# schematic.net
KiCad netlist of a schematic drawn in Altium Designer
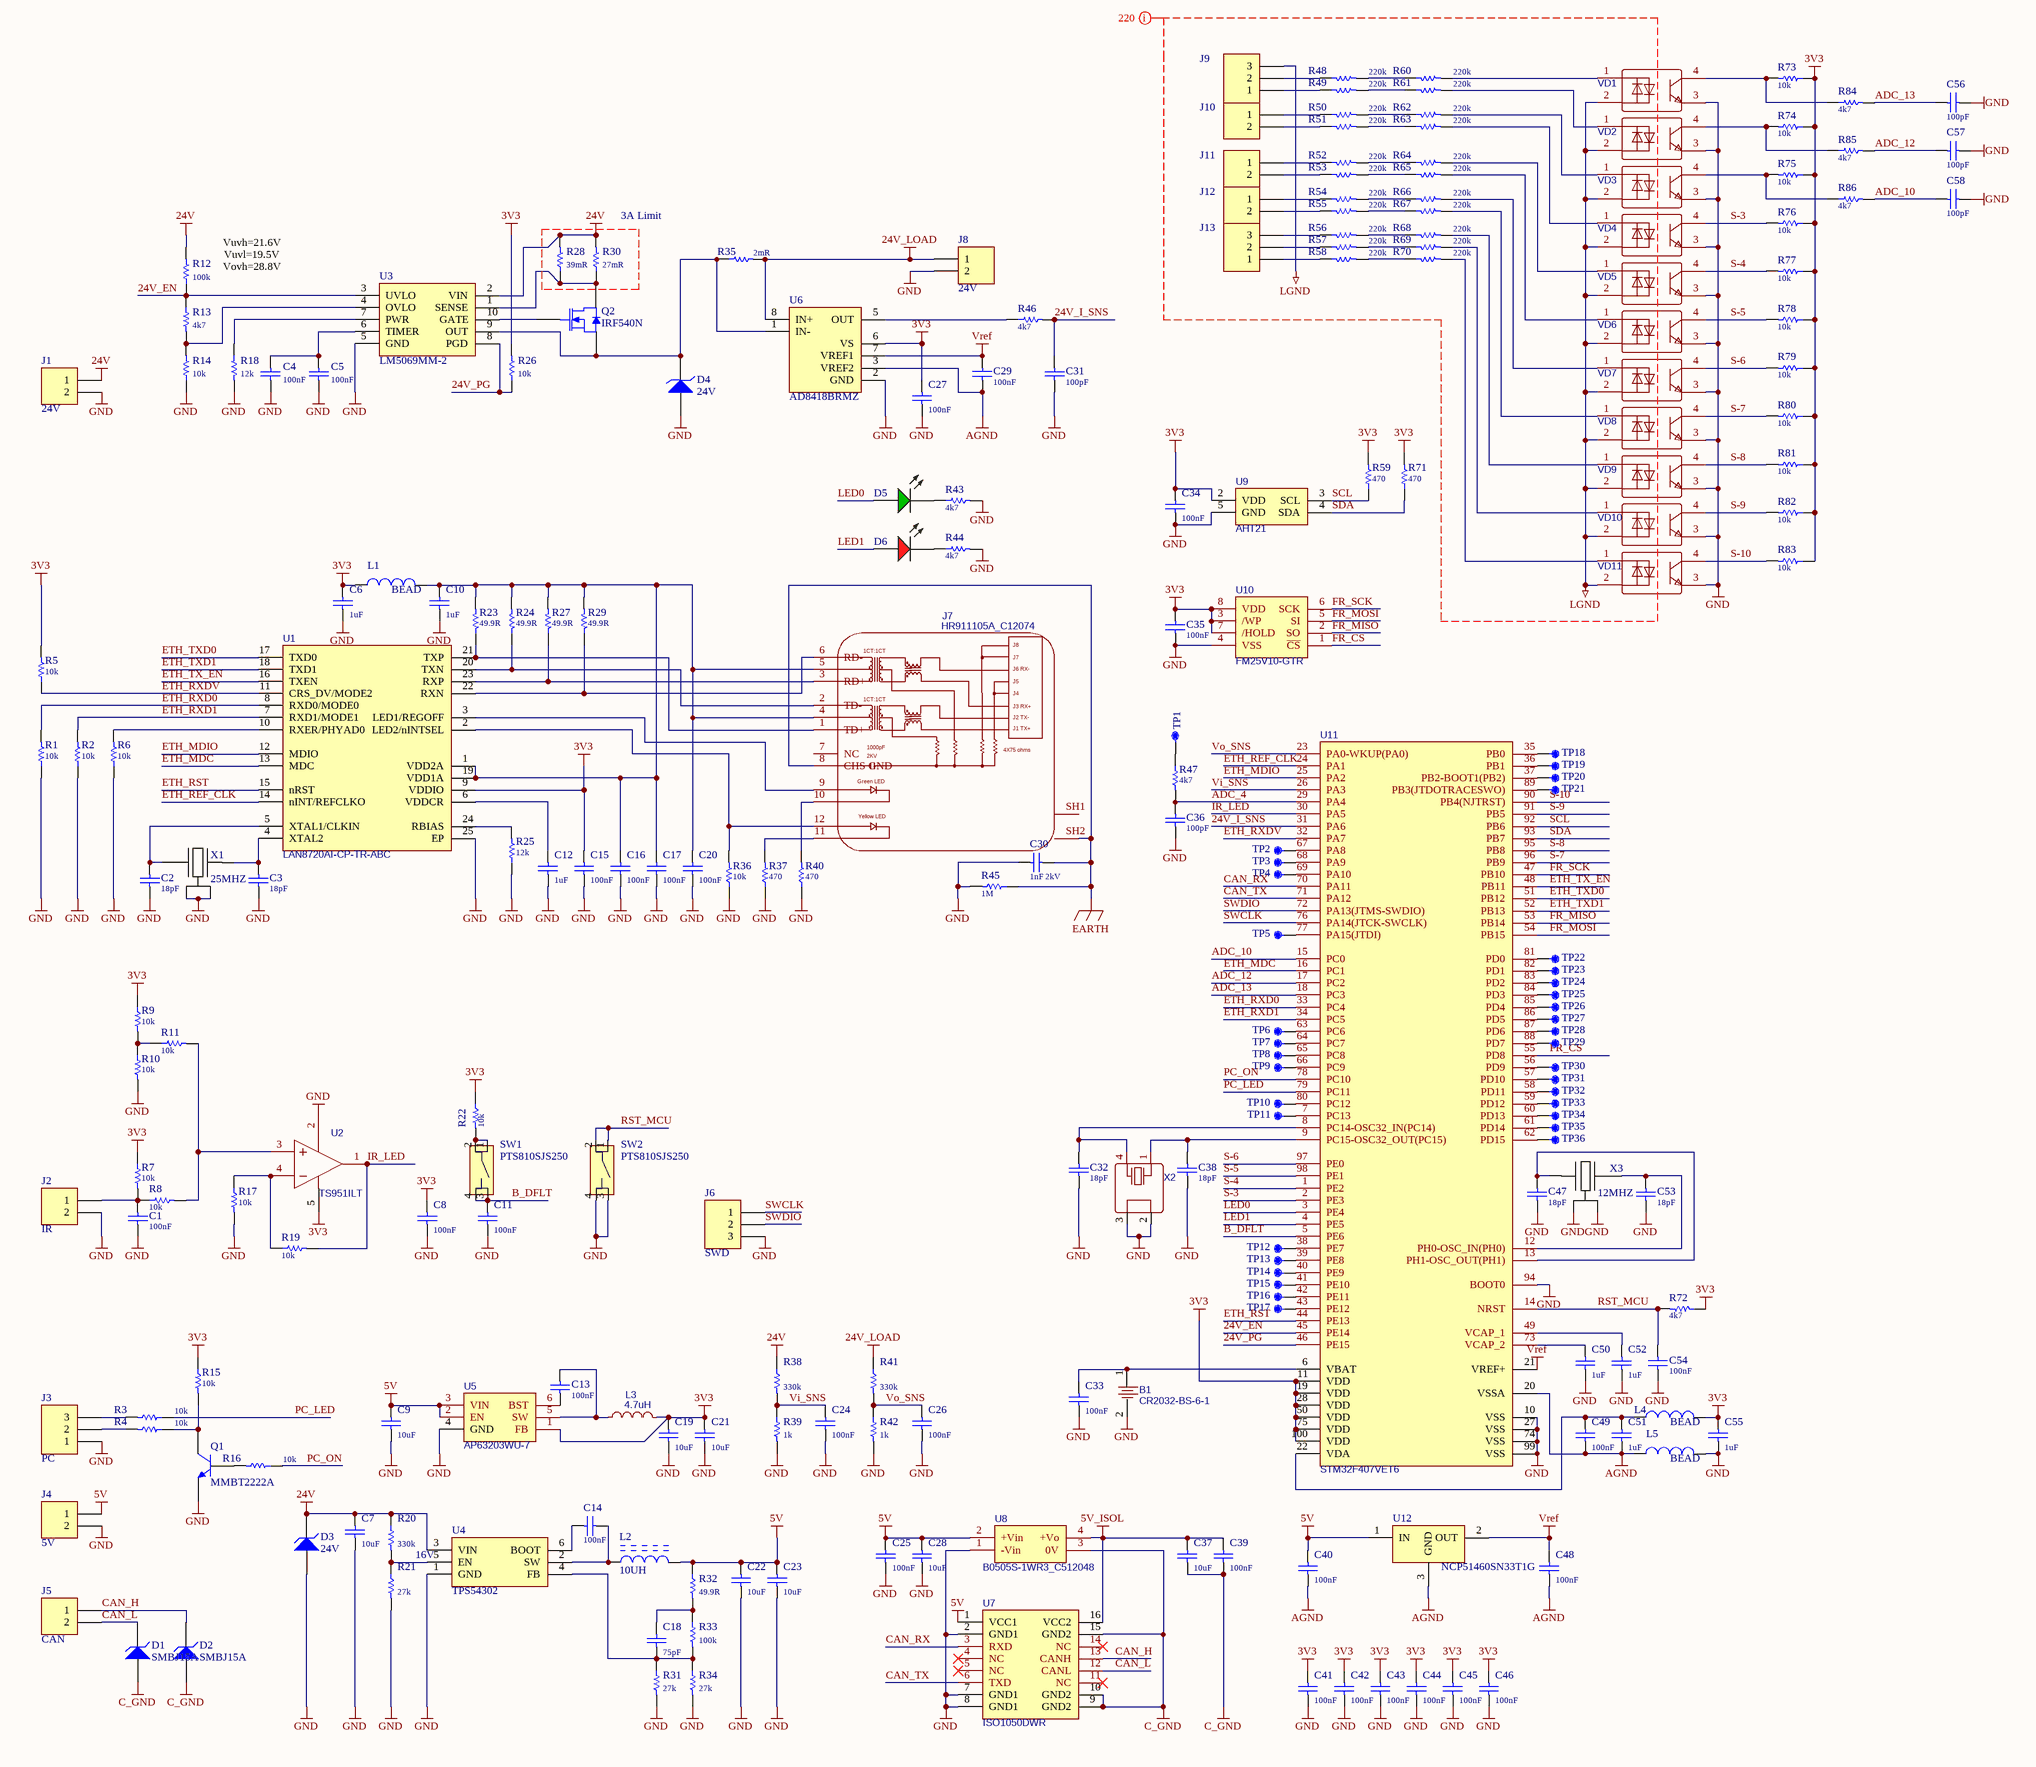
[diagram p0: schematic.SchDoc]

(export (version "E")
  (design (tool "Eeschema 10.0.6"))
  (components
    (comp (ref "B1")
      (value "CR2032-BS-6-1")
      (footprint "BAT-TH_CR2032-BS-6-1")
      (libsource (lib "altium-import") (part "root_3_CR2032-BS-6-1_"))
    )
    (comp (ref "C1")
      (value "100nF")
      (footprint "C0603")
      (description "100nF 0603")
      (libsource (lib "Miscellaneous Devices") (part "CAP"))
    )
    (comp (ref "C2")
      (value "18pF")
      (footprint "C0402")
      (description "10pF 0402")
      (libsource (lib "Miscellaneous Devices") (part "CAP"))
    )
    (comp (ref "C3")
      (value "18pF")
      (footprint "C0402")
      (description "10pF 0402")
      (libsource (lib "Miscellaneous Devices") (part "CAP"))
    )
    (comp (ref "C4")
      (value "100nF")
      (footprint "C0402")
      (description "100nF 0402")
      (libsource (lib "Miscellaneous Devices") (part "CAP"))
    )
    (comp (ref "C5")
      (value "100nF")
      (footprint "C0402")
      (description "100nF 0402")
      (libsource (lib "Miscellaneous Devices") (part "CAP"))
    )
    (comp (ref "C6")
      (value "1uF")
      (footprint "C0603")
      (description "1uF 0603")
      (libsource (lib "Miscellaneous Devices") (part "CAP"))
    )
    (comp (ref "C7")
      (value "10uF")
      (footprint "C1206")
      (description "10uF 1206")
      (libsource (lib "Miscellaneous Devices") (part "CAP"))
    )
    (comp (ref "C8")
      (value "100nF")
      (footprint "C0402")
      (description "100nF 0402")
      (libsource (lib "Miscellaneous Devices") (part "CAP"))
    )
    (comp (ref "C9")
      (value "10uF")
      (footprint "C1206")
      (description "10uF 1206")
      (libsource (lib "Miscellaneous Devices") (part "CAP"))
    )
    (comp (ref "C10")
      (value "1uF")
      (footprint "C0603")
      (description "1uF 0603")
      (libsource (lib "Miscellaneous Devices") (part "CAP"))
    )
    (comp (ref "C11")
      (value "100nF")
      (footprint "C0402")
      (description "100nF 0402")
      (libsource (lib "Miscellaneous Devices") (part "CAP"))
    )
    (comp (ref "C12")
      (value "1uF")
      (footprint "C0603")
      (description "1uF 0603")
      (libsource (lib "Miscellaneous Devices") (part "CAP"))
    )
    (comp (ref "C13")
      (value "100nF")
      (footprint "C0402")
      (description "100nF 0402")
      (libsource (lib "Miscellaneous Devices") (part "CAP"))
    )
    (comp (ref "C14")
      (value "100nF")
      (footprint "C0603")
      (description "100nF 0603")
      (libsource (lib "Miscellaneous Devices") (part "CAP"))
    )
    (comp (ref "C15")
      (value "100nF")
      (footprint "C0402")
      (description "100nF 0402")
      (libsource (lib "Miscellaneous Devices") (part "CAP"))
    )
    (comp (ref "C16")
      (value "100nF")
      (footprint "C0402")
      (description "100nF 0402")
      (libsource (lib "Miscellaneous Devices") (part "CAP"))
    )
    (comp (ref "C17")
      (value "100nF")
      (footprint "C0402")
      (description "100nF 0402")
      (libsource (lib "Miscellaneous Devices") (part "CAP"))
    )
    (comp (ref "C18")
      (value "75pF")
      (footprint "C0603")
      (description "75pF 0603")
      (libsource (lib "Miscellaneous Devices") (part "CAP"))
    )
    (comp (ref "C19")
      (value "10uF")
      (footprint "C1206")
      (description "10uF 1206")
      (libsource (lib "Miscellaneous Devices") (part "CAP"))
    )
    (comp (ref "C20")
      (value "100nF")
      (footprint "C0402")
      (description "100nF 0402")
      (libsource (lib "Miscellaneous Devices") (part "CAP"))
    )
    (comp (ref "C21")
      (value "10uF")
      (footprint "C1206")
      (description "10uF 1206")
      (libsource (lib "Miscellaneous Devices") (part "CAP"))
    )
    (comp (ref "C22")
      (value "10uF")
      (footprint "C1206")
      (description "10uF 1206")
      (libsource (lib "Miscellaneous Devices") (part "CAP"))
    )
    (comp (ref "C23")
      (value "10uF")
      (footprint "C1206")
      (description "10uF 1206")
      (libsource (lib "Miscellaneous Devices") (part "CAP"))
    )
    (comp (ref "C24")
      (value "100nF")
      (footprint "C0603")
      (description "100nF 0603")
      (libsource (lib "Miscellaneous Devices") (part "CAP"))
    )
    (comp (ref "C25")
      (value "100nF")
      (footprint "C0402")
      (description "100nF 0402")
      (libsource (lib "Miscellaneous Devices") (part "CAP"))
    )
    (comp (ref "C26")
      (value "100nF")
      (footprint "C0603")
      (description "100nF 0603")
      (libsource (lib "Miscellaneous Devices") (part "CAP"))
    )
    (comp (ref "C27")
      (value "100nF")
      (footprint "C0402")
      (description "100nF 0402")
      (libsource (lib "Miscellaneous Devices") (part "CAP"))
    )
    (comp (ref "C28")
      (value "10uF")
      (footprint "C1206")
      (description "10uF 1206")
      (libsource (lib "Miscellaneous Devices") (part "CAP"))
    )
    (comp (ref "C29")
      (value "100nF")
      (footprint "C0402")
      (description "100nF 0402")
      (libsource (lib "Miscellaneous Devices") (part "CAP"))
    )
    (comp (ref "C30")
      (value "1nF 2kV")
      (footprint "C1206")
      (description "1nF 2kV 1206")
      (libsource (lib "Miscellaneous Devices") (part "CAP"))
    )
    (comp (ref "C31")
      (value "100pF")
      (footprint "C0402")
      (description "100pF 0402")
      (libsource (lib "Miscellaneous Devices") (part "CAP"))
    )
    (comp (ref "C32")
      (value "18pF")
      (footprint "C0402")
      (description "10pF 0402")
      (libsource (lib "Miscellaneous Devices") (part "CAP"))
    )
    (comp (ref "C33")
      (value "100nF")
      (footprint "C0402")
      (description "100nF 0402")
      (libsource (lib "Miscellaneous Devices") (part "CAP"))
    )
    (comp (ref "C34")
      (value "100nF")
      (footprint "C0402")
      (description "100nF 0402")
      (libsource (lib "Miscellaneous Devices") (part "CAP"))
    )
    (comp (ref "C35")
      (value "100nF")
      (footprint "C0402")
      (description "100nF 0402")
      (libsource (lib "Miscellaneous Devices") (part "CAP"))
    )
    (comp (ref "C36")
      (value "100pF")
      (footprint "C0402")
      (description "100pF 0402")
      (libsource (lib "Miscellaneous Devices") (part "CAP"))
    )
    (comp (ref "C37")
      (value "10uF")
      (footprint "C1206")
      (description "10uF 1206")
      (libsource (lib "Miscellaneous Devices") (part "CAP"))
    )
    (comp (ref "C38")
      (value "18pF")
      (footprint "C0402")
      (description "10pF 0402")
      (libsource (lib "Miscellaneous Devices") (part "CAP"))
    )
    (comp (ref "C39")
      (value "100nF")
      (footprint "C0402")
      (description "100nF 0402")
      (libsource (lib "Miscellaneous Devices") (part "CAP"))
    )
    (comp (ref "C40")
      (value "100nF")
      (footprint "C0402")
      (description "100nF 0402")
      (libsource (lib "Miscellaneous Devices") (part "CAP"))
    )
    (comp (ref "C41")
      (value "100nF")
      (footprint "C0402")
      (description "100nF 0402")
      (libsource (lib "Miscellaneous Devices") (part "CAP"))
    )
    (comp (ref "C42")
      (value "100nF")
      (footprint "C0402")
      (description "100nF 0402")
      (libsource (lib "Miscellaneous Devices") (part "CAP"))
    )
    (comp (ref "C43")
      (value "100nF")
      (footprint "C0402")
      (description "100nF 0402")
      (libsource (lib "Miscellaneous Devices") (part "CAP"))
    )
    (comp (ref "C44")
      (value "100nF")
      (footprint "C0402")
      (description "100nF 0402")
      (libsource (lib "Miscellaneous Devices") (part "CAP"))
    )
    (comp (ref "C45")
      (value "100nF")
      (footprint "C0402")
      (description "100nF 0402")
      (libsource (lib "Miscellaneous Devices") (part "CAP"))
    )
    (comp (ref "C46")
      (value "100nF")
      (footprint "C0402")
      (description "100nF 0402")
      (libsource (lib "Miscellaneous Devices") (part "CAP"))
    )
    (comp (ref "C47")
      (value "18pF")
      (footprint "C0402")
      (description "10pF 0402")
      (libsource (lib "Miscellaneous Devices") (part "CAP"))
    )
    (comp (ref "C48")
      (value "100nF")
      (footprint "C0402")
      (description "100nF 0402")
      (libsource (lib "Miscellaneous Devices") (part "CAP"))
    )
    (comp (ref "C49")
      (value "100nF")
      (footprint "C0402")
      (description "100nF 0402")
      (libsource (lib "Miscellaneous Devices") (part "CAP"))
    )
    (comp (ref "C50")
      (value "1uF")
      (footprint "C0603")
      (description "1uF 0603")
      (libsource (lib "Miscellaneous Devices") (part "CAP"))
    )
    (comp (ref "C51")
      (value "1uF")
      (footprint "C0603")
      (description "1uF 0603")
      (libsource (lib "Miscellaneous Devices") (part "CAP"))
    )
    (comp (ref "C52")
      (value "1uF")
      (footprint "C0603")
      (description "1uF 0603")
      (libsource (lib "Miscellaneous Devices") (part "CAP"))
    )
    (comp (ref "C53")
      (value "18pF")
      (footprint "C0402")
      (description "10pF 0402")
      (libsource (lib "Miscellaneous Devices") (part "CAP"))
    )
    (comp (ref "C54")
      (value "100nF")
      (footprint "C0402")
      (description "100nF 0402")
      (libsource (lib "Miscellaneous Devices") (part "CAP"))
    )
    (comp (ref "C55")
      (value "1uF")
      (footprint "C0603")
      (description "1uF 0603")
      (libsource (lib "Miscellaneous Devices") (part "CAP"))
    )
    (comp (ref "C56")
      (value "100pF")
      (footprint "C0402")
      (description "100pF 0402")
      (libsource (lib "Miscellaneous Devices") (part "CAP"))
    )
    (comp (ref "C57")
      (value "100pF")
      (footprint "C0402")
      (description "100pF 0402")
      (libsource (lib "Miscellaneous Devices") (part "CAP"))
    )
    (comp (ref "C58")
      (value "100pF")
      (footprint "C0402")
      (description "100pF 0402")
      (libsource (lib "Miscellaneous Devices") (part "CAP"))
    )
    (comp (ref "D1")
      (value "SMBJ15A")
      (footprint "SMB")
      (libsource (lib "Miscellaneous Devices") (part "SMCJ54A"))
    )
    (comp (ref "D2")
      (value "SMBJ15A")
      (footprint "SMB")
      (libsource (lib "Miscellaneous Devices") (part "SMCJ54A"))
    )
    (comp (ref "D3")
      (value "24V")
      (footprint "SMB")
      (description "P6SMB24A")
      (libsource (lib "Miscellaneous Devices") (part "SMCJ54A"))
    )
    (comp (ref "D4")
      (value "24V")
      (footprint "SMC")
      (description "1.5SMC24A-E3/57T")
      (libsource (lib "Miscellaneous Devices") (part "NCP51460SN33T1G"))
    )
    (comp (ref "D5")
      (value "GRN")
      (footprint "LED-0603-GRN")
      (description "LED 0603 GRN")
      (libsource (lib "Miscellaneous Devices") (part "LED-0603-GREEN"))
    )
    (comp (ref "D6")
      (value "RED")
      (footprint "LED-0603-RED")
      (description "LED 0603 RED")
      (libsource (lib "Miscellaneous Devices") (part "LED-0603-RED"))
    )
    (comp (ref "J1")
      (value "24V")
      (footprint "CONN-TH_2P-P5.08")
      (libsource (lib "Miscellaneous Devices") (part "CONN MOLEX HDR-M 1x4"))
    )
    (comp (ref "J2")
      (value "IR")
      (footprint "CONN-TH_2P-P5.08")
      (libsource (lib "Miscellaneous Devices") (part "CONN MOLEX HDR-M 1x4"))
    )
    (comp (ref "J3")
      (value "PC")
      (footprint "CONN-TH_DB127V-5.08-3P")
      (libsource (lib "Miscellaneous Connectors") (part "CONN MOLEX HDR-M 1x12"))
    )
    (comp (ref "J4")
      (value "5V")
      (footprint "CONN-TH_2P-P5.08")
      (libsource (lib "Miscellaneous Devices") (part "CONN MOLEX HDR-M 1x4"))
    )
    (comp (ref "J5")
      (value "CAN")
      (footprint "CONN-TH_2P-P5.08")
      (libsource (lib "Miscellaneous Devices") (part "CONN MOLEX HDR-M 1x4"))
    )
    (comp (ref "J6")
      (value "SWD")
      (footprint "HDR-1X3")
      (libsource (lib "Miscellaneous Devices") (part "Header 3"))
    )
    (comp (ref "J7")
      (value "HR911105A_C12074")
      (footprint "RJ45-TH_HR911105A")
      (libsource (lib "altium-import") (part "root_0_HR911105A_C12074_"))
    )
    (comp (ref "J8")
      (value "24V")
      (footprint "CONN-TH_2P-P5.08")
      (libsource (lib "") (part "CONN MOLEX HDR-M 1x4_1"))
    )
    (comp (ref "J9")
      (value "~")
      (footprint "CONN-TH_DB127V-5.08-3P")
      (libsource (lib "Miscellaneous Connectors") (part "CONN MOLEX HDR-M 1x12"))
    )
    (comp (ref "J10")
      (value "~")
      (footprint "CONN-TH_2P-P5.08")
      (libsource (lib "Miscellaneous Devices") (part "CONN MOLEX HDR-M 1x4"))
    )
    (comp (ref "J11")
      (value "~")
      (footprint "CONN-TH_2P-P5.08")
      (libsource (lib "Miscellaneous Devices") (part "CONN MOLEX HDR-M 1x4"))
    )
    (comp (ref "J12")
      (value "~")
      (footprint "CONN-TH_2P-P5.08")
      (libsource (lib "Miscellaneous Devices") (part "CONN MOLEX HDR-M 1x4"))
    )
    (comp (ref "J13")
      (value "~")
      (footprint "CONN-TH_DB127V-5.08-3P")
      (libsource (lib "Miscellaneous Connectors") (part "CONN MOLEX HDR-M 1x12"))
    )
    (comp (ref "L1")
      (value "BEAD")
      (footprint "L0603")
      (description "BEAD 0402")
      (libsource (lib "Miscellaneous Devices") (part "BLM18AG601SN1D"))
    )
    (comp (ref "L2")
      (value "10UH")
      (footprint "IND-SMD_L7.2-W6.6_GPSR07X0")
      (description "CYA0630-10UH")
      (libsource (lib "Miscellaneous Devices") (part "SRN3015-100M"))
    )
    (comp (ref "L3")
      (value "4.7uH")
      (footprint "IND-SMD_L4.4-W4.2")
      (description "FXL0420-4R7-M")
      (libsource (lib "altium-import") (part "root_0_4.7uH_"))
    )
    (comp (ref "L4")
      (value "BEAD")
      (footprint "L0402")
      (description "BEAD 0402")
      (libsource (lib "Miscellaneous Devices") (part "BLM18AG601SN1D"))
    )
    (comp (ref "L5")
      (value "BEAD")
      (footprint "L0402")
      (description "BEAD 0402")
      (libsource (lib "Miscellaneous Devices") (part "BLM18AG601SN1D"))
    )
    (comp (ref "Q1")
      (value "MMBT2222A")
      (footprint "SOT-23")
      (description "MMBT2222")
      (libsource (lib "Miscellaneous Devices") (part "MMBT2222ALT1G"))
    )
    (comp (ref "Q2")
      (value "IRF540N")
      (footprint "D2PAK")
      (libsource (lib "Miscellaneous Devices") (part "BSC123N10LSGATMA1"))
    )
    (comp (ref "R1")
      (value "10k")
      (footprint "R0402")
      (description "10k 0402")
      (libsource (lib "RR_Passive") (part "RES"))
    )
    (comp (ref "R2")
      (value "10k")
      (footprint "R0402")
      (description "10k 0402")
      (libsource (lib "RR_Passive") (part "RES"))
    )
    (comp (ref "R3")
      (value "10k")
      (footprint "R0603")
      (description "10k 0603")
      (libsource (lib "RR_Passive") (part "RES"))
    )
    (comp (ref "R4")
      (value "10k")
      (footprint "R0603")
      (description "10k 0603")
      (libsource (lib "RR_Passive") (part "RES"))
    )
    (comp (ref "R5")
      (value "10k")
      (footprint "R0402")
      (description "10k 0402")
      (libsource (lib "RR_Passive") (part "RES"))
    )
    (comp (ref "R6")
      (value "10k")
      (footprint "R0402")
      (description "10k 0402")
      (libsource (lib "RR_Passive") (part "RES"))
    )
    (comp (ref "R7")
      (value "10k")
      (footprint "R0603")
      (description "10k 0603")
      (libsource (lib "RR_Passive") (part "RES"))
    )
    (comp (ref "R8")
      (value "10k")
      (footprint "R0603")
      (description "10k 0603")
      (libsource (lib "RR_Passive") (part "RES"))
    )
    (comp (ref "R9")
      (value "10k")
      (footprint "R0603")
      (description "10k 0603")
      (libsource (lib "RR_Passive") (part "RES"))
    )
    (comp (ref "R10")
      (value "10k")
      (footprint "R0603")
      (description "10k 0603")
      (libsource (lib "RR_Passive") (part "RES"))
    )
    (comp (ref "R11")
      (value "10k")
      (footprint "R0603")
      (description "10k 0603")
      (libsource (lib "RR_Passive") (part "RES"))
    )
    (comp (ref "R12")
      (value "100k")
      (footprint "R0402")
      (description "100k 0402")
      (libsource (lib "") (part "RES_2"))
    )
    (comp (ref "R13")
      (value "4k7")
      (footprint "R0402")
      (description "4k7 0402")
      (libsource (lib "Miscellaneous Devices") (part "RES"))
    )
    (comp (ref "R14")
      (value "10k")
      (footprint "R0402")
      (description "10k 0402")
      (libsource (lib "") (part "RES_2"))
    )
    (comp (ref "R15")
      (value "10k")
      (footprint "R0603")
      (description "10k 0603")
      (libsource (lib "RR_Passive") (part "RES"))
    )
    (comp (ref "R16")
      (value "10k")
      (footprint "R0603")
      (description "10k 0603")
      (libsource (lib "RR_Passive") (part "RES"))
    )
    (comp (ref "R17")
      (value "10k")
      (footprint "R0603")
      (description "10k 0603")
      (libsource (lib "RR_Passive") (part "RES"))
    )
    (comp (ref "R18")
      (value "12k")
      (footprint "R0603")
      (description "12k 0603")
      (libsource (lib "Miscellaneous Devices") (part "RES"))
    )
    (comp (ref "R19")
      (value "10k")
      (footprint "R0603")
      (description "10k 0603")
      (libsource (lib "RR_Passive") (part "RES"))
    )
    (comp (ref "R20")
      (value "330k")
      (footprint "R0603")
      (description "330k 0603")
      (libsource (lib "Miscellaneous Devices") (part "RES"))
    )
    (comp (ref "R21")
      (value "27k")
      (footprint "R0603")
      (description "27k 0603")
      (libsource (lib "Miscellaneous Devices") (part "RES"))
    )
    (comp (ref "R22")
      (value "10k")
      (footprint "R0402")
      (description "10k 0402")
      (libsource (lib "") (part "RES_2"))
    )
    (comp (ref "R23")
      (value "49.9R")
      (footprint "R0603")
      (description "49.9R 0603")
      (libsource (lib "Miscellaneous Devices") (part "RES"))
    )
    (comp (ref "R24")
      (value "49.9R")
      (footprint "R0603")
      (description "49.9R 0603")
      (libsource (lib "Miscellaneous Devices") (part "RES"))
    )
    (comp (ref "R25")
      (value "12k")
      (footprint "R0402")
      (description "12k 0402")
      (libsource (lib "Miscellaneous Devices") (part "RES"))
    )
    (comp (ref "R26")
      (value "10k")
      (footprint "R0402")
      (description "10k 0402")
      (libsource (lib "") (part "RES_2"))
    )
    (comp (ref "R27")
      (value "49.9R")
      (footprint "R0603")
      (description "49.9R 0603")
      (libsource (lib "Miscellaneous Devices") (part "RES"))
    )
    (comp (ref "R28")
      (value "39mR")
      (footprint "R1206")
      (description "39mR 1206")
      (libsource (lib "") (part "RES_2"))
    )
    (comp (ref "R29")
      (value "49.9R")
      (footprint "R0603")
      (description "49.9R 0603")
      (libsource (lib "Miscellaneous Devices") (part "RES"))
    )
    (comp (ref "R30")
      (value "27mR")
      (footprint "R1206")
      (description "27mR 1206")
      (libsource (lib "") (part "RES_2"))
    )
    (comp (ref "R31")
      (value "27k")
      (footprint "R0603")
      (description "27k 0603")
      (libsource (lib "Miscellaneous Devices") (part "RES"))
    )
    (comp (ref "R32")
      (value "49.9R")
      (footprint "R0603")
      (description "49.9R 0603")
      (libsource (lib "") (part "RES_1"))
    )
    (comp (ref "R33")
      (value "100k")
      (footprint "R0603")
      (description "100k 0603")
      (libsource (lib "Miscellaneous Devices") (part "RES"))
    )
    (comp (ref "R34")
      (value "27k")
      (footprint "R0603")
      (description "27k 0603")
      (libsource (lib "Miscellaneous Devices") (part "RES"))
    )
    (comp (ref "R35")
      (value "2mR")
      (footprint "R2512-WIDE")
      (description "2mR shunt 2512")
      (libsource (lib "Miscellaneous Devices") (part "RES"))
    )
    (comp (ref "R36")
      (value "10k")
      (footprint "R0603")
      (description "10k 0603")
      (libsource (lib "RR_Passive") (part "RES"))
    )
    (comp (ref "R37")
      (value "470")
      (footprint "R0603")
      (description "470R 0603")
      (libsource (lib "RR_Passive") (part "RES"))
    )
    (comp (ref "R38")
      (value "330k")
      (footprint "R0603")
      (description "330k 0603")
      (libsource (lib "Miscellaneous Devices") (part "RES"))
    )
    (comp (ref "R39")
      (value "1k")
      (footprint "R0603")
      (description "1k 0603")
      (libsource (lib "") (part "RES_1"))
    )
    (comp (ref "R40")
      (value "470")
      (footprint "R0603")
      (description "470R 0603")
      (libsource (lib "RR_Passive") (part "RES"))
    )
    (comp (ref "R41")
      (value "330k")
      (footprint "R0603")
      (description "330k 0603")
      (libsource (lib "Miscellaneous Devices") (part "RES"))
    )
    (comp (ref "R42")
      (value "1k")
      (footprint "R0603")
      (description "1k 0603")
      (libsource (lib "") (part "RES_1"))
    )
    (comp (ref "R43")
      (value "4k7")
      (footprint "R0402")
      (description "4k7 0402")
      (libsource (lib "Miscellaneous Devices") (part "RES"))
    )
    (comp (ref "R44")
      (value "4k7")
      (footprint "R0402")
      (description "4k7 0402")
      (libsource (lib "Miscellaneous Devices") (part "RES"))
    )
    (comp (ref "R45")
      (value "1M")
      (footprint "R1206")
      (description "1M 1206")
      (libsource (lib "RR_Passive") (part "RES"))
    )
    (comp (ref "R46")
      (value "4k7")
      (footprint "R0402")
      (description "4k7 0402")
      (libsource (lib "Miscellaneous Devices") (part "RES"))
    )
    (comp (ref "R47")
      (value "4k7")
      (footprint "R0402")
      (description "4k7 0402")
      (libsource (lib "Miscellaneous Devices") (part "RES"))
    )
    (comp (ref "R48")
      (value "220k")
      (footprint "R1206")
      (description "220k 1206")
      (libsource (lib "Miscellaneous Devices") (part "RES"))
    )
    (comp (ref "R49")
      (value "220k")
      (footprint "R1206")
      (description "220k 1206")
      (libsource (lib "Miscellaneous Devices") (part "RES"))
    )
    (comp (ref "R50")
      (value "220k")
      (footprint "R1206")
      (description "220k 1206")
      (libsource (lib "Miscellaneous Devices") (part "RES"))
    )
    (comp (ref "R51")
      (value "220k")
      (footprint "R1206")
      (description "220k 1206")
      (libsource (lib "Miscellaneous Devices") (part "RES"))
    )
    (comp (ref "R52")
      (value "220k")
      (footprint "R1206")
      (description "220k 1206")
      (libsource (lib "Miscellaneous Devices") (part "RES"))
    )
    (comp (ref "R53")
      (value "220k")
      (footprint "R1206")
      (description "220k 1206")
      (libsource (lib "Miscellaneous Devices") (part "RES"))
    )
    (comp (ref "R54")
      (value "220k")
      (footprint "R1206")
      (description "220k 1206")
      (libsource (lib "Miscellaneous Devices") (part "RES"))
    )
    (comp (ref "R55")
      (value "220k")
      (footprint "R1206")
      (description "220k 1206")
      (libsource (lib "Miscellaneous Devices") (part "RES"))
    )
    (comp (ref "R56")
      (value "220k")
      (footprint "R1206")
      (description "220k 1206")
      (libsource (lib "Miscellaneous Devices") (part "RES"))
    )
    (comp (ref "R57")
      (value "220k")
      (footprint "R1206")
      (description "220k 1206")
      (libsource (lib "Miscellaneous Devices") (part "RES"))
    )
    (comp (ref "R58")
      (value "220k")
      (footprint "R1206")
      (description "220k 1206")
      (libsource (lib "Miscellaneous Devices") (part "RES"))
    )
    (comp (ref "R59")
      (value "470")
      (footprint "R0603")
      (description "470R 0603")
      (libsource (lib "RR_Passive") (part "RES"))
    )
    (comp (ref "R60")
      (value "220k")
      (footprint "R1206")
      (description "220k 1206")
      (libsource (lib "Miscellaneous Devices") (part "RES"))
    )
    (comp (ref "R61")
      (value "220k")
      (footprint "R1206")
      (description "220k 1206")
      (libsource (lib "Miscellaneous Devices") (part "RES"))
    )
    (comp (ref "R62")
      (value "220k")
      (footprint "R1206")
      (description "220k 1206")
      (libsource (lib "Miscellaneous Devices") (part "RES"))
    )
    (comp (ref "R63")
      (value "220k")
      (footprint "R1206")
      (description "220k 1206")
      (libsource (lib "Miscellaneous Devices") (part "RES"))
    )
    (comp (ref "R64")
      (value "220k")
      (footprint "R1206")
      (description "220k 1206")
      (libsource (lib "Miscellaneous Devices") (part "RES"))
    )
    (comp (ref "R65")
      (value "220k")
      (footprint "R1206")
      (description "220k 1206")
      (libsource (lib "Miscellaneous Devices") (part "RES"))
    )
    (comp (ref "R66")
      (value "220k")
      (footprint "R1206")
      (description "220k 1206")
      (libsource (lib "Miscellaneous Devices") (part "RES"))
    )
    (comp (ref "R67")
      (value "220k")
      (footprint "R1206")
      (description "220k 1206")
      (libsource (lib "Miscellaneous Devices") (part "RES"))
    )
    (comp (ref "R68")
      (value "220k")
      (footprint "R1206")
      (description "220k 1206")
      (libsource (lib "Miscellaneous Devices") (part "RES"))
    )
    (comp (ref "R69")
      (value "220k")
      (footprint "R1206")
      (description "220k 1206")
      (libsource (lib "Miscellaneous Devices") (part "RES"))
    )
    (comp (ref "R70")
      (value "220k")
      (footprint "R1206")
      (description "220k 1206")
      (libsource (lib "Miscellaneous Devices") (part "RES"))
    )
    (comp (ref "R71")
      (value "470")
      (footprint "R0603")
      (description "470R 0603")
      (libsource (lib "RR_Passive") (part "RES"))
    )
    (comp (ref "R72")
      (value "4k7")
      (footprint "R0402")
      (description "4k7 0402")
      (libsource (lib "Miscellaneous Devices") (part "RES"))
    )
    (comp (ref "R73")
      (value "10k")
      (footprint "R0603")
      (description "10k 0603")
      (libsource (lib "RR_Passive") (part "RES"))
    )
    (comp (ref "R74")
      (value "10k")
      (footprint "R0603")
      (description "10k 0603")
      (libsource (lib "RR_Passive") (part "RES"))
    )
    (comp (ref "R75")
      (value "10k")
      (footprint "R0603")
      (description "10k 0603")
      (libsource (lib "RR_Passive") (part "RES"))
    )
    (comp (ref "R76")
      (value "10k")
      (footprint "R0603")
      (description "10k 0603")
      (libsource (lib "RR_Passive") (part "RES"))
    )
    (comp (ref "R77")
      (value "10k")
      (footprint "R0603")
      (description "10k 0603")
      (libsource (lib "RR_Passive") (part "RES"))
    )
    (comp (ref "R78")
      (value "10k")
      (footprint "R0603")
      (description "10k 0603")
      (libsource (lib "RR_Passive") (part "RES"))
    )
    (comp (ref "R79")
      (value "10k")
      (footprint "R0603")
      (description "10k 0603")
      (libsource (lib "RR_Passive") (part "RES"))
    )
    (comp (ref "R80")
      (value "10k")
      (footprint "R0603")
      (description "10k 0603")
      (libsource (lib "RR_Passive") (part "RES"))
    )
    (comp (ref "R81")
      (value "10k")
      (footprint "R0603")
      (description "10k 0603")
      (libsource (lib "RR_Passive") (part "RES"))
    )
    (comp (ref "R82")
      (value "10k")
      (footprint "R0603")
      (description "10k 0603")
      (libsource (lib "RR_Passive") (part "RES"))
    )
    (comp (ref "R83")
      (value "10k")
      (footprint "R0603")
      (description "10k 0603")
      (libsource (lib "RR_Passive") (part "RES"))
    )
    (comp (ref "R84")
      (value "4k7")
      (footprint "R0402")
      (description "4k7 0402")
      (libsource (lib "Miscellaneous Devices") (part "RES"))
    )
    (comp (ref "R85")
      (value "4k7")
      (footprint "R0402")
      (description "4k7 0402")
      (libsource (lib "Miscellaneous Devices") (part "RES"))
    )
    (comp (ref "R86")
      (value "4k7")
      (footprint "R0402")
      (description "4k7 0402")
      (libsource (lib "Miscellaneous Devices") (part "RES"))
    )
    (comp (ref "SW1")
      (value "PTS810SJS250")
      (footprint "BTN_PTS810")
      (libsource (lib "Miscellaneous Devices") (part "Component_1"))
    )
    (comp (ref "SW2")
      (value "PTS810SJS250")
      (footprint "BTN_PTS810")
      (libsource (lib "Miscellaneous Devices") (part "Component_1"))
    )
    (comp (ref "TP1")
      (value "~")
      (footprint "TP_TH_MICRO")
      (libsource (lib "Miscellaneous Devices") (part "TP_Dup1"))
    )
    (comp (ref "TP2")
      (value "~")
      (footprint "TP_TH_MICRO")
      (libsource (lib "Miscellaneous Devices") (part "TP_Dup1"))
    )
    (comp (ref "TP3")
      (value "~")
      (footprint "TP_TH_MICRO")
      (libsource (lib "Miscellaneous Devices") (part "TP_Dup1"))
    )
    (comp (ref "TP4")
      (value "~")
      (footprint "TP_TH_MICRO")
      (libsource (lib "Miscellaneous Devices") (part "TP_Dup1"))
    )
    (comp (ref "TP5")
      (value "~")
      (footprint "TP_TH_MICRO")
      (libsource (lib "Miscellaneous Devices") (part "TP_Dup1"))
    )
    (comp (ref "TP6")
      (value "~")
      (footprint "TP_TH_MICRO")
      (libsource (lib "Miscellaneous Devices") (part "TP_Dup1"))
    )
    (comp (ref "TP7")
      (value "~")
      (footprint "TP_TH_MICRO")
      (libsource (lib "Miscellaneous Devices") (part "TP_Dup1"))
    )
    (comp (ref "TP8")
      (value "~")
      (footprint "TP_TH_MICRO")
      (libsource (lib "Miscellaneous Devices") (part "TP_Dup1"))
    )
    (comp (ref "TP9")
      (value "~")
      (footprint "TP_TH_MICRO")
      (libsource (lib "Miscellaneous Devices") (part "TP_Dup1"))
    )
    (comp (ref "TP10")
      (value "~")
      (footprint "TP_TH_MICRO")
      (libsource (lib "Miscellaneous Devices") (part "TP_Dup1"))
    )
    (comp (ref "TP11")
      (value "~")
      (footprint "TP_TH_MICRO")
      (libsource (lib "Miscellaneous Devices") (part "TP_Dup1"))
    )
    (comp (ref "TP12")
      (value "~")
      (footprint "TP_TH_MICRO")
      (libsource (lib "Miscellaneous Devices") (part "TP_Dup1"))
    )
    (comp (ref "TP13")
      (value "~")
      (footprint "TP_TH_MICRO")
      (libsource (lib "Miscellaneous Devices") (part "TP_Dup1"))
    )
    (comp (ref "TP14")
      (value "~")
      (footprint "TP_TH_MICRO")
      (libsource (lib "Miscellaneous Devices") (part "TP_Dup1"))
    )
    (comp (ref "TP15")
      (value "~")
      (footprint "TP_TH_MICRO")
      (libsource (lib "Miscellaneous Devices") (part "TP_Dup1"))
    )
    (comp (ref "TP16")
      (value "~")
      (footprint "TP_TH_MICRO")
      (libsource (lib "Miscellaneous Devices") (part "TP_Dup1"))
    )
    (comp (ref "TP17")
      (value "~")
      (footprint "TP_TH_MICRO")
      (libsource (lib "Miscellaneous Devices") (part "TP_Dup1"))
    )
    (comp (ref "TP18")
      (value "~")
      (footprint "TP_TH_MICRO")
      (libsource (lib "Miscellaneous Devices") (part "TP_Dup1"))
    )
    (comp (ref "TP19")
      (value "~")
      (footprint "TP_TH_MICRO")
      (libsource (lib "Miscellaneous Devices") (part "TP_Dup1"))
    )
    (comp (ref "TP20")
      (value "~")
      (footprint "TP_TH_MICRO")
      (libsource (lib "Miscellaneous Devices") (part "TP_Dup1"))
    )
    (comp (ref "TP21")
      (value "~")
      (footprint "TP_TH_MICRO")
      (libsource (lib "Miscellaneous Devices") (part "TP_Dup1"))
    )
    (comp (ref "TP22")
      (value "~")
      (footprint "TP_TH_MICRO")
      (libsource (lib "Miscellaneous Devices") (part "TP_Dup1"))
    )
    (comp (ref "TP23")
      (value "~")
      (footprint "TP_TH_MICRO")
      (libsource (lib "Miscellaneous Devices") (part "TP_Dup1"))
    )
    (comp (ref "TP24")
      (value "~")
      (footprint "TP_TH_MICRO")
      (libsource (lib "Miscellaneous Devices") (part "TP_Dup1"))
    )
    (comp (ref "TP25")
      (value "~")
      (footprint "TP_TH_MICRO")
      (libsource (lib "Miscellaneous Devices") (part "TP_Dup1"))
    )
    (comp (ref "TP26")
      (value "~")
      (footprint "TP_TH_MICRO")
      (libsource (lib "Miscellaneous Devices") (part "TP_Dup1"))
    )
    (comp (ref "TP27")
      (value "~")
      (footprint "TP_TH_MICRO")
      (libsource (lib "Miscellaneous Devices") (part "TP_Dup1"))
    )
    (comp (ref "TP28")
      (value "~")
      (footprint "TP_TH_MICRO")
      (libsource (lib "Miscellaneous Devices") (part "TP_Dup1"))
    )
    (comp (ref "TP29")
      (value "~")
      (footprint "TP_TH_MICRO")
      (libsource (lib "Miscellaneous Devices") (part "TP_Dup1"))
    )
    (comp (ref "TP30")
      (value "~")
      (footprint "TP_TH_MICRO")
      (libsource (lib "Miscellaneous Devices") (part "TP_Dup1"))
    )
    (comp (ref "TP31")
      (value "~")
      (footprint "TP_TH_MICRO")
      (libsource (lib "Miscellaneous Devices") (part "TP_Dup1"))
    )
    (comp (ref "TP32")
      (value "~")
      (footprint "TP_TH_MICRO")
      (libsource (lib "Miscellaneous Devices") (part "TP_Dup1"))
    )
    (comp (ref "TP33")
      (value "~")
      (footprint "TP_TH_MICRO")
      (libsource (lib "Miscellaneous Devices") (part "TP_Dup1"))
    )
    (comp (ref "TP34")
      (value "~")
      (footprint "TP_TH_MICRO")
      (libsource (lib "Miscellaneous Devices") (part "TP_Dup1"))
    )
    (comp (ref "TP35")
      (value "~")
      (footprint "TP_TH_MICRO")
      (libsource (lib "Miscellaneous Devices") (part "TP_Dup1"))
    )
    (comp (ref "TP36")
      (value "~")
      (footprint "TP_TH_MICRO")
      (libsource (lib "Miscellaneous Devices") (part "TP_Dup1"))
    )
    (comp (ref "U1")
      (value "LAN8720AI-CP-TR-ABC")
      (footprint "QFN-24_L4.0-W4.0-P0.50-TL-EP2.5")
      (libsource (lib "Schlib1") (part "LAN8720AI-CP-TR-ABC"))
    )
    (comp (ref "U2")
      (value "TS951ILT")
      (footprint "SOT-23-5")
      (libsource (lib "altium-import") (part "root_2_mirrored_TS951ILT_"))
    )
    (comp (ref "U3")
      (value "LM5069MM-2")
      (footprint "VSSOP-10 (3x3x0.5)")
      (libsource (lib "Schlib1") (part "TPS2491"))
    )
    (comp (ref "U4")
      (value "TPS54302")
      (footprint "SOT-23-6")
      (description "TPS54302DDCR")
      (libsource (lib "Miscellaneous Devices") (part "LM27313XMFX"))
    )
    (comp (ref "U5")
      (value "AP63203WU-7")
      (footprint "SOT-23-6")
      (libsource (lib "Schlib1") (part "AP63203WU-7"))
    )
    (comp (ref "U6") (value "AD8418BRMZ") (footprint "MSOP8") (libsource (lib "schlib") (part "AD8418BRMZ")))
    (comp (ref "U7")
      (value "ISO1050DWR")
      (footprint "SOIC-16_L10.3-W7.5-P1.27-LS10.3-BL")
      (libsource (lib "STM32F429BIT6") (part "ISO1050DWR"))
    )
    (comp (ref "U8")
      (value "B0505S-1WR3_C512048")
      (footprint "PWRM-TH_BXXXXS-1WR3")
      (libsource (lib "Schlib1") (part "B0505S-1WR3_C512048"))
    )
    (comp (ref "U9")
      (value "AHT21")
      (footprint "SENSOR-SMD_L3.0-W3.0-P1.00-BR")
      (libsource (lib "Schlib1") (part "AHT21"))
    )
    (comp (ref "U10")
      (value "FM25V10-GTR")
      (footprint "SOIC-8")
      (libsource (lib "Schlib1") (part "FM25V10-GTR"))
    )
    (comp (ref "U11")
      (value "STM32F407VET6")
      (footprint "LQFP-100")
      (libsource (lib "Schlib1") (part "STM32F407VET6"))
    )
    (comp (ref "U12")
      (value "NCP51460SN33T1G")
      (footprint "SOT-23")
      (libsource (lib "Schlib1") (part "NCP51460SN33T1G"))
    )
    (comp (ref "VD1")
      (value "EL3H4(A)(TA)-VG")
      (footprint "SOP-4_L4.4-W2.8-P1.27-LS7.0-TL")
      (libsource (lib "altium-import") (part "root_0_EL3H4(A)(TA)-VG_"))
    )
    (comp (ref "VD2")
      (value "EL3H4(A)(TA)-VG")
      (footprint "SOP-4_L4.4-W2.8-P1.27-LS7.0-TL")
      (libsource (lib "altium-import") (part "root_0_EL3H4(A)(TA)-VG_"))
    )
    (comp (ref "VD3")
      (value "EL3H4(A)(TA)-VG")
      (footprint "SOP-4_L4.4-W2.8-P1.27-LS7.0-TL")
      (libsource (lib "altium-import") (part "root_0_EL3H4(A)(TA)-VG_"))
    )
    (comp (ref "VD4")
      (value "EL3H4(A)(TA)-VG")
      (footprint "SOP-4_L4.4-W2.8-P1.27-LS7.0-TL")
      (libsource (lib "altium-import") (part "root_0_EL3H4(A)(TA)-VG_"))
    )
    (comp (ref "VD5")
      (value "EL3H4(A)(TA)-VG")
      (footprint "SOP-4_L4.4-W2.8-P1.27-LS7.0-TL")
      (libsource (lib "altium-import") (part "root_0_EL3H4(A)(TA)-VG_"))
    )
    (comp (ref "VD6")
      (value "EL3H4(A)(TA)-VG")
      (footprint "SOP-4_L4.4-W2.8-P1.27-LS7.0-TL")
      (libsource (lib "altium-import") (part "root_0_EL3H4(A)(TA)-VG_"))
    )
    (comp (ref "VD7")
      (value "EL3H4(A)(TA)-VG")
      (footprint "SOP-4_L4.4-W2.8-P1.27-LS7.0-TL")
      (libsource (lib "altium-import") (part "root_0_EL3H4(A)(TA)-VG_"))
    )
    (comp (ref "VD8")
      (value "EL3H4(A)(TA)-VG")
      (footprint "SOP-4_L4.4-W2.8-P1.27-LS7.0-TL")
      (libsource (lib "altium-import") (part "root_0_EL3H4(A)(TA)-VG_"))
    )
    (comp (ref "VD9")
      (value "EL3H4(A)(TA)-VG")
      (footprint "SOP-4_L4.4-W2.8-P1.27-LS7.0-TL")
      (libsource (lib "altium-import") (part "root_0_EL3H4(A)(TA)-VG_"))
    )
    (comp (ref "VD10")
      (value "EL3H4(A)(TA)-VG")
      (footprint "SOP-4_L4.4-W2.8-P1.27-LS7.0-TL")
      (libsource (lib "altium-import") (part "root_0_EL3H4(A)(TA)-VG_"))
    )
    (comp (ref "VD11")
      (value "EL3H4(A)(TA)-VG")
      (footprint "SOP-4_L4.4-W2.8-P1.27-LS7.0-TL")
      (libsource (lib "altium-import") (part "root_0_EL3H4(A)(TA)-VG_"))
    )
    (comp (ref "X1")
      (value "25MHZ")
      (footprint "CRYSTAL_3.2x2.5mm")
      (description "X322525MOB4SI")
      (libsource (lib "Miscellaneous Devices") (part "CRYSTAL 12MHZ 3.20mm x 2.50mm"))
    )
    (comp (ref "X2") (value "32.768kHz") (footprint "MC-146") (libsource (lib "Schlib1") (part "32.768kHz")))
    (comp (ref "X3")
      (value "12MHZ")
      (footprint "CRYSTAL_3.2x2.5mm")
      (description "X322512MOB4SI")
      (libsource (lib "Miscellaneous Devices") (part "CRYSTAL 12MHZ 3.20mm x 2.50mm"))
    )
  )
  (nets
    (net (code "1") (name "/24V_EN") (class "Default")
      (node (ref "R12") (pin "1") (pinfunction "1_1") (pintype "passive"))
      (node (ref "R13") (pin "1") (pinfunction "1_1") (pintype "passive"))
      (node (ref "U11") (pin "45") (pinfunction "PE14_45") (pintype "passive"))
      (node (ref "U3") (pin "3") (pinfunction "UVLO_3") (pintype "passive"))
    )
    (net (code "2") (name "/24V_I_SNS") (class "Default")
      (node (ref "C31") (pin "1") (pinfunction "1_1") (pintype "passive"))
      (node (ref "R46") (pin "2") (pinfunction "2_2") (pintype "passive"))
      (node (ref "U11") (pin "31") (pinfunction "PA6_31") (pintype "passive"))
    )
    (net (code "3") (name "/24V_PG") (class "Default")
      (node (ref "R26") (pin "1") (pinfunction "1_1") (pintype "passive"))
      (node (ref "U11") (pin "46") (pinfunction "PE15_46") (pintype "passive"))
      (node (ref "U3") (pin "8") (pinfunction "PGD_8") (pintype "passive"))
    )
    (net (code "4") (name "/ADC_4") (class "Default")
      (node (ref "C36") (pin "2") (pinfunction "2_2") (pintype "passive"))
      (node (ref "R47") (pin "2") (pinfunction "2_2") (pintype "passive"))
      (node (ref "U11") (pin "29") (pinfunction "PA4_29") (pintype "passive"))
    )
    (net (code "5") (name "/ADC_10") (class "Default")
      (node (ref "C58") (pin "2") (pinfunction "2_2") (pintype "passive"))
      (node (ref "R86") (pin "2") (pinfunction "2_2") (pintype "passive"))
      (node (ref "U11") (pin "15") (pinfunction "PC0_15") (pintype "passive"))
    )
    (net (code "6") (name "/ADC_12") (class "Default")
      (node (ref "C57") (pin "2") (pinfunction "2_2") (pintype "passive"))
      (node (ref "R85") (pin "2") (pinfunction "2_2") (pintype "passive"))
      (node (ref "U11") (pin "17") (pinfunction "PC2_17") (pintype "passive"))
    )
    (net (code "7") (name "/ADC_13") (class "Default")
      (node (ref "C56") (pin "2") (pinfunction "2_2") (pintype "passive"))
      (node (ref "R84") (pin "2") (pinfunction "2_2") (pintype "passive"))
      (node (ref "U11") (pin "18") (pinfunction "PC3_18") (pintype "passive"))
    )
    (net (code "8") (name "/B_DFLT") (class "Default")
      (node (ref "C11") (pin "2") (pinfunction "2_2") (pintype "passive"))
      (node (ref "SW1") (pin "3") (pinfunction "3_3") (pintype "passive"))
      (node (ref "SW1") (pin "4") (pinfunction "4_4") (pintype "passive"))
      (node (ref "U11") (pin "5") (pinfunction "PE6_5") (pintype "passive"))
    )
    (net (code "9") (name "/CAN_H") (class "Default")
      (node (ref "D2") (pin "2") (pinfunction "K_2") (pintype "passive"))
      (node (ref "J5") (pin "1") (pinfunction "1_1") (pintype "passive"))
      (node (ref "U7") (pin "13") (pinfunction "CANH_13") (pintype "passive"))
    )
    (net (code "10") (name "/CAN_L") (class "Default")
      (node (ref "D1") (pin "2") (pinfunction "K_2") (pintype "passive"))
      (node (ref "J5") (pin "2") (pinfunction "2_2") (pintype "passive"))
      (node (ref "U7") (pin "12") (pinfunction "CANL_12") (pintype "passive"))
    )
    (net (code "11") (name "/CAN_RX") (class "Default")
      (node (ref "U11") (pin "70") (pinfunction "PA11_70") (pintype "passive"))
      (node (ref "U7") (pin "3") (pinfunction "RXD_3") (pintype "passive"))
    )
    (net (code "12") (name "/CAN_TX") (class "Default")
      (node (ref "U11") (pin "71") (pinfunction "PA12_71") (pintype "passive"))
      (node (ref "U7") (pin "6") (pinfunction "TXD_6") (pintype "passive"))
    )
    (net (code "13") (name "/ETH_MDC") (class "Default")
      (node (ref "U1") (pin "13") (pinfunction "MDC_13") (pintype "passive"))
      (node (ref "U11") (pin "16") (pinfunction "PC1_16") (pintype "passive"))
    )
    (net (code "14") (name "/ETH_MDIO") (class "Default")
      (node (ref "U1") (pin "12") (pinfunction "MDIO_12") (pintype "passive"))
      (node (ref "U11") (pin "25") (pinfunction "PA2_25") (pintype "passive"))
    )
    (net (code "15") (name "/ETH_REF_CLK") (class "Default")
      (node (ref "U1") (pin "14") (pinfunction "nINT/REFCLKO_14") (pintype "passive"))
      (node (ref "U11") (pin "24") (pinfunction "PA1_24") (pintype "passive"))
    )
    (net (code "16") (name "/ETH_RST") (class "Default")
      (node (ref "U1") (pin "15") (pinfunction "nRST_15") (pintype "passive"))
      (node (ref "U11") (pin "44") (pinfunction "PE13_44") (pintype "passive"))
    )
    (net (code "17") (name "/ETH_RXD0") (class "Default")
      (node (ref "R1") (pin "2") (pinfunction "2_2") (pintype "passive"))
      (node (ref "U1") (pin "8") (pinfunction "RXD0/MODE0_8") (pintype "passive"))
      (node (ref "U11") (pin "33") (pinfunction "PC4_33") (pintype "passive"))
    )
    (net (code "18") (name "/ETH_RXD1") (class "Default")
      (node (ref "R2") (pin "2") (pinfunction "2_2") (pintype "passive"))
      (node (ref "U1") (pin "7") (pinfunction "RXD1/MODE1_7") (pintype "passive"))
      (node (ref "U11") (pin "34") (pinfunction "PC5_34") (pintype "passive"))
    )
    (net (code "19") (name "/ETH_RXDV") (class "Default")
      (node (ref "R5") (pin "1") (pinfunction "1_1") (pintype "passive"))
      (node (ref "U1") (pin "11") (pinfunction "CRS_DV/MODE2_11") (pintype "passive"))
      (node (ref "U11") (pin "32") (pinfunction "PA7_32") (pintype "passive"))
    )
    (net (code "20") (name "/ETH_TXD0") (class "Default")
      (node (ref "U1") (pin "17") (pinfunction "TXD0_17") (pintype "passive"))
      (node (ref "U11") (pin "51") (pinfunction "PB12_51") (pintype "passive"))
    )
    (net (code "21") (name "/ETH_TXD1") (class "Default")
      (node (ref "U1") (pin "18") (pinfunction "TXD1_18") (pintype "passive"))
      (node (ref "U11") (pin "52") (pinfunction "PB13_52") (pintype "passive"))
    )
    (net (code "22") (name "/ETH_TX_EN") (class "Default")
      (node (ref "U1") (pin "16") (pinfunction "TXEN_16") (pintype "passive"))
      (node (ref "U11") (pin "48") (pinfunction "PB11_48") (pintype "passive"))
    )
    (net (code "23") (name "/FR_CS") (class "Default")
      (node (ref "U10") (pin "1") (pinfunction "~{CS}_1") (pintype "passive"))
      (node (ref "U11") (pin "55") (pinfunction "PD8_55") (pintype "passive"))
    )
    (net (code "24") (name "/FR_MISO") (class "Default")
      (node (ref "U10") (pin "2") (pinfunction "SO_2") (pintype "passive"))
      (node (ref "U11") (pin "53") (pinfunction "PB14_53") (pintype "passive"))
    )
    (net (code "25") (name "/FR_MOSI") (class "Default")
      (node (ref "U10") (pin "5") (pinfunction "SI_5") (pintype "passive"))
      (node (ref "U11") (pin "54") (pinfunction "PB15_54") (pintype "passive"))
    )
    (net (code "26") (name "/FR_SCK") (class "Default")
      (node (ref "U10") (pin "6") (pinfunction "SCK_6") (pintype "passive"))
      (node (ref "U11") (pin "47") (pinfunction "PB10_47") (pintype "passive"))
    )
    (net (code "27") (name "/IR_LED") (class "Default")
      (node (ref "R19") (pin "2") (pinfunction "2_2") (pintype "passive"))
      (node (ref "U11") (pin "30") (pinfunction "PA5_30") (pintype "passive"))
      (node (ref "U2") (pin "1") (pinfunction "OUT_1") (pintype "passive"))
    )
    (net (code "28") (name "/LED0") (class "Default")
      (node (ref "D5") (pin "1") (pinfunction "A_1") (pintype "passive"))
      (node (ref "U11") (pin "3") (pinfunction "PE4_3") (pintype "passive"))
    )
    (net (code "29") (name "/LED1") (class "Default")
      (node (ref "D6") (pin "1") (pinfunction "A_1") (pintype "passive"))
      (node (ref "U11") (pin "4") (pinfunction "PE5_4") (pintype "passive"))
    )
    (net (code "30") (name "/PC_LED") (class "Default")
      (node (ref "R3") (pin "1") (pinfunction "1_1") (pintype "passive"))
      (node (ref "U11") (pin "79") (pinfunction "PC11_79") (pintype "passive"))
    )
    (net (code "31") (name "/PC_ON") (class "Default")
      (node (ref "R16") (pin "1") (pinfunction "1_1") (pintype "passive"))
      (node (ref "U11") (pin "78") (pinfunction "PC10_78") (pintype "passive"))
    )
    (net (code "32") (name "/RST_MCU") (class "Default")
      (node (ref "C54") (pin "2") (pinfunction "2_2") (pintype "passive"))
      (node (ref "R72") (pin "2") (pinfunction "2_2") (pintype "passive"))
      (node (ref "SW2") (pin "1") (pinfunction "1_1") (pintype "passive"))
      (node (ref "SW2") (pin "2") (pinfunction "2_2") (pintype "passive"))
      (node (ref "U11") (pin "14") (pinfunction "NRST_14") (pintype "passive"))
    )
    (net (code "33") (name "/S-3") (class "Default")
      (node (ref "R76") (pin "2") (pinfunction "2_2") (pintype "passive"))
      (node (ref "U11") (pin "2") (pinfunction "PE3_2") (pintype "passive"))
      (node (ref "VD4") (pin "4") (pinfunction "Collector_4") (pintype "passive"))
    )
    (net (code "34") (name "/S-4") (class "Default")
      (node (ref "R77") (pin "2") (pinfunction "2_2") (pintype "passive"))
      (node (ref "U11") (pin "1") (pinfunction "PE2_1") (pintype "passive"))
      (node (ref "VD5") (pin "4") (pinfunction "Collector_4") (pintype "passive"))
    )
    (net (code "35") (name "/S-5") (class "Default")
      (node (ref "R78") (pin "2") (pinfunction "2_2") (pintype "passive"))
      (node (ref "U11") (pin "98") (pinfunction "PE1_98") (pintype "passive"))
      (node (ref "VD6") (pin "4") (pinfunction "Collector_4") (pintype "passive"))
    )
    (net (code "36") (name "/S-6") (class "Default")
      (node (ref "R79") (pin "2") (pinfunction "2_2") (pintype "passive"))
      (node (ref "U11") (pin "97") (pinfunction "PE0_97") (pintype "passive"))
      (node (ref "VD7") (pin "4") (pinfunction "Collector_4") (pintype "passive"))
    )
    (net (code "37") (name "/S-7") (class "Default")
      (node (ref "R80") (pin "2") (pinfunction "2_2") (pintype "passive"))
      (node (ref "U11") (pin "96") (pinfunction "PB9_96") (pintype "passive"))
      (node (ref "VD8") (pin "4") (pinfunction "Collector_4") (pintype "passive"))
    )
    (net (code "38") (name "/S-8") (class "Default")
      (node (ref "R81") (pin "2") (pinfunction "2_2") (pintype "passive"))
      (node (ref "U11") (pin "95") (pinfunction "PB8_95") (pintype "passive"))
      (node (ref "VD9") (pin "4") (pinfunction "Collector_4") (pintype "passive"))
    )
    (net (code "39") (name "/S-9") (class "Default")
      (node (ref "R82") (pin "2") (pinfunction "2_2") (pintype "passive"))
      (node (ref "U11") (pin "91") (pinfunction "PB5_91") (pintype "passive"))
      (node (ref "VD10") (pin "4") (pinfunction "Collector_4") (pintype "passive"))
    )
    (net (code "40") (name "/S-10") (class "Default")
      (node (ref "R83") (pin "2") (pinfunction "2_2") (pintype "passive"))
      (node (ref "U11") (pin "90") (pinfunction "PB4(NJTRST)_90") (pintype "passive"))
      (node (ref "VD11") (pin "4") (pinfunction "Collector_4") (pintype "passive"))
    )
    (net (code "41") (name "/SCL") (class "Default")
      (node (ref "R59") (pin "1") (pinfunction "1_1") (pintype "passive"))
      (node (ref "U11") (pin "92") (pinfunction "PB6_92") (pintype "passive"))
      (node (ref "U9") (pin "3") (pinfunction "SCL_3") (pintype "passive"))
    )
    (net (code "42") (name "/SDA") (class "Default")
      (node (ref "R71") (pin "1") (pinfunction "1_1") (pintype "passive"))
      (node (ref "U11") (pin "93") (pinfunction "PB7_93") (pintype "passive"))
      (node (ref "U9") (pin "4") (pinfunction "SDA_4") (pintype "passive"))
    )
    (net (code "43") (name "/SWCLK") (class "Default")
      (node (ref "J6") (pin "1") (pinfunction "1_1") (pintype "passive"))
      (node (ref "U11") (pin "76") (pinfunction "PA14(JTCK-SWCLK)_76") (pintype "passive"))
    )
    (net (code "44") (name "/SWDIO") (class "Default")
      (node (ref "J6") (pin "2") (pinfunction "2_2") (pintype "passive"))
      (node (ref "U11") (pin "72") (pinfunction "PA13(JTMS-SWDIO)_72") (pintype "passive"))
    )
    (net (code "45") (name "/Vi_SNS") (class "Default")
      (node (ref "C24") (pin "2") (pinfunction "2_2") (pintype "passive"))
      (node (ref "R38") (pin "2") (pinfunction "2_2") (pintype "passive"))
      (node (ref "R39") (pin "1") (pinfunction "1_1") (pintype "passive"))
      (node (ref "U11") (pin "26") (pinfunction "PA3_26") (pintype "passive"))
    )
    (net (code "46") (name "/Vo_SNS") (class "Default")
      (node (ref "C26") (pin "2") (pinfunction "2_2") (pintype "passive"))
      (node (ref "R41") (pin "2") (pinfunction "2_2") (pintype "passive"))
      (node (ref "R42") (pin "1") (pinfunction "1_1") (pintype "passive"))
      (node (ref "U11") (pin "23") (pinfunction "PA0-WKUP(PA0)_23") (pintype "passive"))
    )
    (net (code "47") (name "3V3") (class "Default")
      (node (ref "C15") (pin "2") (pinfunction "2_2") (pintype "passive"))
      (node (ref "C19") (pin "2") (pinfunction "2_2") (pintype "passive"))
      (node (ref "C21") (pin "2") (pinfunction "2_2") (pintype "passive"))
      (node (ref "C27") (pin "2") (pinfunction "2_2") (pintype "passive"))
      (node (ref "C34") (pin "2") (pinfunction "2_2") (pintype "passive"))
      (node (ref "C35") (pin "2") (pinfunction "2_2") (pintype "passive"))
      (node (ref "C41") (pin "2") (pinfunction "2_2") (pintype "passive"))
      (node (ref "C42") (pin "2") (pinfunction "2_2") (pintype "passive"))
      (node (ref "C43") (pin "2") (pinfunction "2_2") (pintype "passive"))
      (node (ref "C44") (pin "2") (pinfunction "2_2") (pintype "passive"))
      (node (ref "C45") (pin "2") (pinfunction "2_2") (pintype "passive"))
      (node (ref "C46") (pin "2") (pinfunction "2_2") (pintype "passive"))
      (node (ref "C55") (pin "2") (pinfunction "2_2") (pintype "passive"))
      (node (ref "C6") (pin "2") (pinfunction "2_2") (pintype "passive"))
      (node (ref "C8") (pin "2") (pinfunction "2_2") (pintype "passive"))
      (node (ref "L1") (pin "2") (pinfunction "2_2") (pintype "passive"))
      (node (ref "L3") (pin "2") (pinfunction "2_2") (pintype "passive"))
      (node (ref "L4") (pin "1") (pinfunction "1_1") (pintype "passive"))
      (node (ref "R15") (pin "1") (pinfunction "1_1") (pintype "passive"))
      (node (ref "R22") (pin "1") (pinfunction "1_1") (pintype "passive"))
      (node (ref "R26") (pin "2") (pinfunction "2_2") (pintype "passive"))
      (node (ref "R5") (pin "2") (pinfunction "2_2") (pintype "passive"))
      (node (ref "R59") (pin "2") (pinfunction "2_2") (pintype "passive"))
      (node (ref "R7") (pin "1") (pinfunction "1_1") (pintype "passive"))
      (node (ref "R71") (pin "2") (pinfunction "2_2") (pintype "passive"))
      (node (ref "R72") (pin "1") (pinfunction "1_1") (pintype "passive"))
      (node (ref "R73") (pin "1") (pinfunction "1_1") (pintype "passive"))
      (node (ref "R74") (pin "1") (pinfunction "1_1") (pintype "passive"))
      (node (ref "R75") (pin "1") (pinfunction "1_1") (pintype "passive"))
      (node (ref "R76") (pin "1") (pinfunction "1_1") (pintype "passive"))
      (node (ref "R77") (pin "1") (pinfunction "1_1") (pintype "passive"))
      (node (ref "R78") (pin "1") (pinfunction "1_1") (pintype "passive"))
      (node (ref "R79") (pin "1") (pinfunction "1_1") (pintype "passive"))
      (node (ref "R80") (pin "1") (pinfunction "1_1") (pintype "passive"))
      (node (ref "R81") (pin "1") (pinfunction "1_1") (pintype "passive"))
      (node (ref "R82") (pin "1") (pinfunction "1_1") (pintype "passive"))
      (node (ref "R83") (pin "1") (pinfunction "1_1") (pintype "passive"))
      (node (ref "R9") (pin "1") (pinfunction "1_1") (pintype "passive"))
      (node (ref "U1") (pin "9") (pinfunction "VDDIO_9") (pintype "passive"))
      (node (ref "U10") (pin "3") (pinfunction "/WP_3") (pintype "passive"))
      (node (ref "U10") (pin "7") (pinfunction "/HOLD_7") (pintype "passive"))
      (node (ref "U10") (pin "8") (pinfunction "VDD_8") (pintype "passive"))
      (node (ref "U11") (pin "100") (pinfunction "VDD_100") (pintype "passive"))
      (node (ref "U11") (pin "11") (pinfunction "VDD_11") (pintype "passive"))
      (node (ref "U11") (pin "19") (pinfunction "VDD_19") (pintype "passive"))
      (node (ref "U11") (pin "28") (pinfunction "VDD_28") (pintype "passive"))
      (node (ref "U11") (pin "50") (pinfunction "VDD_50") (pintype "passive"))
      (node (ref "U11") (pin "75") (pinfunction "VDD_75") (pintype "passive"))
      (node (ref "U2") (pin "5") (pinfunction "VCC_5") (pintype "passive"))
      (node (ref "U5") (pin "1") (pinfunction "FB_1") (pintype "passive"))
      (node (ref "U6") (pin "6") (pinfunction "VS_6") (pintype "passive"))
      (node (ref "U9") (pin "2") (pinfunction "VDD_2") (pintype "passive"))
    )
    (net (code "48") (name "5V") (class "Default")
      (node (ref "C22") (pin "2") (pinfunction "2_2") (pintype "passive"))
      (node (ref "C23") (pin "2") (pinfunction "2_2") (pintype "passive"))
      (node (ref "C25") (pin "2") (pinfunction "2_2") (pintype "passive"))
      (node (ref "C28") (pin "2") (pinfunction "2_2") (pintype "passive"))
      (node (ref "C40") (pin "2") (pinfunction "2_2") (pintype "passive"))
      (node (ref "C9") (pin "2") (pinfunction "2_2") (pintype "passive"))
      (node (ref "J4") (pin "1") (pinfunction "1_1") (pintype "passive"))
      (node (ref "L2") (pin "2") (pinfunction "2_2") (pintype "passive"))
      (node (ref "R32") (pin "1") (pinfunction "1_1") (pintype "passive"))
      (node (ref "U12") (pin "1") (pinfunction "IN_1") (pintype "passive"))
      (node (ref "U5") (pin "2") (pinfunction "EN_2") (pintype "passive"))
      (node (ref "U5") (pin "3") (pinfunction "VIN_3") (pintype "passive"))
      (node (ref "U7") (pin "1") (pinfunction "VCC1_1") (pintype "passive"))
      (node (ref "U8") (pin "2") (pinfunction "+Vin_2") (pintype "passive"))
    )
    (net (code "49") (name "5V_ISOL") (class "Default")
      (node (ref "C37") (pin "2") (pinfunction "2_2") (pintype "passive"))
      (node (ref "C39") (pin "2") (pinfunction "2_2") (pintype "passive"))
      (node (ref "U7") (pin "16") (pinfunction "VCC2_16") (pintype "passive"))
      (node (ref "U8") (pin "4") (pinfunction "+Vo_4") (pintype "passive"))
    )
    (net (code "50") (name "24V") (class "Default")
      (node (ref "C7") (pin "2") (pinfunction "2_2") (pintype "passive"))
      (node (ref "D3") (pin "2") (pinfunction "K_2") (pintype "passive"))
      (node (ref "J1") (pin "1") (pinfunction "1_1") (pintype "passive"))
      (node (ref "R12") (pin "2") (pinfunction "2_2") (pintype "passive"))
      (node (ref "R20") (pin "1") (pinfunction "1_1") (pintype "passive"))
      (node (ref "R28") (pin "2") (pinfunction "2_2") (pintype "passive"))
      (node (ref "R30") (pin "2") (pinfunction "2_2") (pintype "passive"))
      (node (ref "R38") (pin "1") (pinfunction "1_1") (pintype "passive"))
      (node (ref "U3") (pin "2") (pinfunction "VIN_2") (pintype "passive"))
      (node (ref "U4") (pin "3") (pinfunction "VIN_3") (pintype "passive"))
    )
    (net (code "51") (name "24V_LOAD") (class "Default")
      (node (ref "J8") (pin "1") (pinfunction "1_1") (pintype "passive"))
      (node (ref "R35") (pin "2") (pinfunction "2_2") (pintype "passive"))
      (node (ref "R41") (pin "1") (pinfunction "1_1") (pintype "passive"))
      (node (ref "U6") (pin "8") (pinfunction "IN+_8") (pintype "passive"))
    )
    (net (code "52") (name "AGND") (class "Default")
      (node (ref "C29") (pin "1") (pinfunction "1_1") (pintype "passive"))
      (node (ref "C40") (pin "1") (pinfunction "1_1") (pintype "passive"))
      (node (ref "C48") (pin "1") (pinfunction "1_1") (pintype "passive"))
      (node (ref "C49") (pin "1") (pinfunction "1_1") (pintype "passive"))
      (node (ref "C51") (pin "1") (pinfunction "1_1") (pintype "passive"))
      (node (ref "L5") (pin "2") (pinfunction "2_2") (pintype "passive"))
      (node (ref "U11") (pin "20") (pinfunction "VSSA_20") (pintype "passive"))
      (node (ref "U12") (pin "3") (pinfunction "GND_3") (pintype "passive"))
      (node (ref "U6") (pin "3") (pinfunction "VREF2_3") (pintype "passive"))
    )
    (net (code "53") (name "C_GND") (class "Default")
      (node (ref "C37") (pin "1") (pinfunction "1_1") (pintype "passive"))
      (node (ref "C39") (pin "1") (pinfunction "1_1") (pintype "passive"))
      (node (ref "D1") (pin "1") (pinfunction "A_1") (pintype "passive"))
      (node (ref "D2") (pin "1") (pinfunction "A_1") (pintype "passive"))
      (node (ref "U7") (pin "10") (pinfunction "GND2_10") (pintype "passive"))
      (node (ref "U7") (pin "15") (pinfunction "GND2_15") (pintype "passive"))
      (node (ref "U7") (pin "9") (pinfunction "GND2_9") (pintype "passive"))
      (node (ref "U8") (pin "3") (pinfunction "0V_3") (pintype "passive"))
    )
    (net (code "54") (name "EARTH") (class "Default")
      (node (ref "C30") (pin "2") (pinfunction "2_2") (pintype "passive"))
      (node (ref "J7") (pin "8") (pinfunction "CHS_GND_8") (pintype "passive"))
      (node (ref "J7") (pin "SH2") (pinfunction "SH2_SH2") (pintype "passive"))
      (node (ref "R45") (pin "1") (pinfunction "1_1") (pintype "passive"))
    )
    (net (code "55") (name "GND") (class "Default")
      (node (ref "B1") (pin "2") (pinfunction "2_2") (pintype "passive"))
      (node (ref "C1") (pin "1") (pinfunction "1_1") (pintype "passive"))
      (node (ref "C10") (pin "1") (pinfunction "1_1") (pintype "passive"))
      (node (ref "C11") (pin "1") (pinfunction "1_1") (pintype "passive"))
      (node (ref "C12") (pin "1") (pinfunction "1_1") (pintype "passive"))
      (node (ref "C15") (pin "1") (pinfunction "1_1") (pintype "passive"))
      (node (ref "C16") (pin "1") (pinfunction "1_1") (pintype "passive"))
      (node (ref "C17") (pin "1") (pinfunction "1_1") (pintype "passive"))
      (node (ref "C19") (pin "1") (pinfunction "1_1") (pintype "passive"))
      (node (ref "C2") (pin "1") (pinfunction "1_1") (pintype "passive"))
      (node (ref "C20") (pin "1") (pinfunction "1_1") (pintype "passive"))
      (node (ref "C21") (pin "1") (pinfunction "1_1") (pintype "passive"))
      (node (ref "C22") (pin "1") (pinfunction "1_1") (pintype "passive"))
      (node (ref "C23") (pin "1") (pinfunction "1_1") (pintype "passive"))
      (node (ref "C24") (pin "1") (pinfunction "1_1") (pintype "passive"))
      (node (ref "C25") (pin "1") (pinfunction "1_1") (pintype "passive"))
      (node (ref "C26") (pin "1") (pinfunction "1_1") (pintype "passive"))
      (node (ref "C27") (pin "1") (pinfunction "1_1") (pintype "passive"))
      (node (ref "C28") (pin "1") (pinfunction "1_1") (pintype "passive"))
      (node (ref "C3") (pin "1") (pinfunction "1_1") (pintype "passive"))
      (node (ref "C30") (pin "1") (pinfunction "1_1") (pintype "passive"))
      (node (ref "C31") (pin "2") (pinfunction "2_2") (pintype "passive"))
      (node (ref "C32") (pin "1") (pinfunction "1_1") (pintype "passive"))
      (node (ref "C33") (pin "1") (pinfunction "1_1") (pintype "passive"))
      (node (ref "C34") (pin "1") (pinfunction "1_1") (pintype "passive"))
      (node (ref "C35") (pin "1") (pinfunction "1_1") (pintype "passive"))
      (node (ref "C36") (pin "1") (pinfunction "1_1") (pintype "passive"))
      (node (ref "C38") (pin "1") (pinfunction "1_1") (pintype "passive"))
      (node (ref "C4") (pin "1") (pinfunction "1_1") (pintype "passive"))
      (node (ref "C41") (pin "1") (pinfunction "1_1") (pintype "passive"))
      (node (ref "C42") (pin "1") (pinfunction "1_1") (pintype "passive"))
      (node (ref "C43") (pin "1") (pinfunction "1_1") (pintype "passive"))
      (node (ref "C44") (pin "1") (pinfunction "1_1") (pintype "passive"))
      (node (ref "C45") (pin "1") (pinfunction "1_1") (pintype "passive"))
      (node (ref "C46") (pin "1") (pinfunction "1_1") (pintype "passive"))
      (node (ref "C47") (pin "1") (pinfunction "1_1") (pintype "passive"))
      (node (ref "C5") (pin "1") (pinfunction "1_1") (pintype "passive"))
      (node (ref "C50") (pin "1") (pinfunction "1_1") (pintype "passive"))
      (node (ref "C52") (pin "1") (pinfunction "1_1") (pintype "passive"))
      (node (ref "C53") (pin "1") (pinfunction "1_1") (pintype "passive"))
      (node (ref "C54") (pin "1") (pinfunction "1_1") (pintype "passive"))
      (node (ref "C55") (pin "1") (pinfunction "1_1") (pintype "passive"))
      (node (ref "C56") (pin "1") (pinfunction "1_1") (pintype "passive"))
      (node (ref "C57") (pin "1") (pinfunction "1_1") (pintype "passive"))
      (node (ref "C58") (pin "1") (pinfunction "1_1") (pintype "passive"))
      (node (ref "C6") (pin "1") (pinfunction "1_1") (pintype "passive"))
      (node (ref "C7") (pin "1") (pinfunction "1_1") (pintype "passive"))
      (node (ref "C8") (pin "1") (pinfunction "1_1") (pintype "passive"))
      (node (ref "C9") (pin "1") (pinfunction "1_1") (pintype "passive"))
      (node (ref "D3") (pin "1") (pinfunction "A_1") (pintype "passive"))
      (node (ref "D4") (pin "2") (pinfunction "-_2") (pintype "passive"))
      (node (ref "J1") (pin "2") (pinfunction "2_2") (pintype "passive"))
      (node (ref "J2") (pin "2") (pinfunction "2_2") (pintype "passive"))
      (node (ref "J3") (pin "1") (pinfunction "1_1") (pintype "passive"))
      (node (ref "J4") (pin "2") (pinfunction "2_2") (pintype "passive"))
      (node (ref "J6") (pin "3") (pinfunction "3_3") (pintype "passive"))
      (node (ref "J8") (pin "2") (pinfunction "2_2") (pintype "passive"))
      (node (ref "L5") (pin "1") (pinfunction "1_1") (pintype "passive"))
      (node (ref "Q1") (pin "2") (pinfunction "E_2") (pintype "passive"))
      (node (ref "R1") (pin "1") (pinfunction "1_1") (pintype "passive"))
      (node (ref "R10") (pin "2") (pinfunction "2_2") (pintype "passive"))
      (node (ref "R14") (pin "1") (pinfunction "1_1") (pintype "passive"))
      (node (ref "R17") (pin "2") (pinfunction "2_2") (pintype "passive"))
      (node (ref "R18") (pin "2") (pinfunction "2_2") (pintype "passive"))
      (node (ref "R2") (pin "1") (pinfunction "1_1") (pintype "passive"))
      (node (ref "R21") (pin "2") (pinfunction "2_2") (pintype "passive"))
      (node (ref "R25") (pin "1") (pinfunction "1_1") (pintype "passive"))
      (node (ref "R31") (pin "2") (pinfunction "2_2") (pintype "passive"))
      (node (ref "R34") (pin "2") (pinfunction "2_2") (pintype "passive"))
      (node (ref "R36") (pin "1") (pinfunction "1_1") (pintype "passive"))
      (node (ref "R37") (pin "1") (pinfunction "1_1") (pintype "passive"))
      (node (ref "R39") (pin "2") (pinfunction "2_2") (pintype "passive"))
      (node (ref "R40") (pin "1") (pinfunction "1_1") (pintype "passive"))
      (node (ref "R42") (pin "2") (pinfunction "2_2") (pintype "passive"))
      (node (ref "R43") (pin "2") (pinfunction "2_2") (pintype "passive"))
      (node (ref "R44") (pin "2") (pinfunction "2_2") (pintype "passive"))
      (node (ref "R45") (pin "2") (pinfunction "2_2") (pintype "passive"))
      (node (ref "R6") (pin "1") (pinfunction "1_1") (pintype "passive"))
      (node (ref "SW2") (pin "3") (pinfunction "3_3") (pintype "passive"))
      (node (ref "SW2") (pin "4") (pinfunction "4_4") (pintype "passive"))
      (node (ref "U1") (pin "25") (pinfunction "EP_25") (pintype "passive"))
      (node (ref "U10") (pin "4") (pinfunction "VSS_4") (pintype "passive"))
      (node (ref "U11") (pin "10") (pinfunction "VSS_10") (pintype "passive"))
      (node (ref "U11") (pin "27") (pinfunction "VSS_27") (pintype "passive"))
      (node (ref "U11") (pin "74") (pinfunction "VSS_74") (pintype "passive"))
      (node (ref "U11") (pin "94") (pinfunction "BOOT0_94") (pintype "passive"))
      (node (ref "U11") (pin "99") (pinfunction "VSS_99") (pintype "passive"))
      (node (ref "U2") (pin "2") (pinfunction "VDD_2") (pintype "passive"))
      (node (ref "U3") (pin "5") (pinfunction "GND_5") (pintype "passive"))
      (node (ref "U4") (pin "1") (pinfunction "GND_1") (pintype "passive"))
      (node (ref "U5") (pin "4") (pinfunction "GND_4") (pintype "passive"))
      (node (ref "U6") (pin "2") (pinfunction "GND_2") (pintype "passive"))
      (node (ref "U7") (pin "2") (pinfunction "GND1_2") (pintype "passive"))
      (node (ref "U7") (pin "7") (pinfunction "GND1_7") (pintype "passive"))
      (node (ref "U7") (pin "8") (pinfunction "GND1_8") (pintype "passive"))
      (node (ref "U8") (pin "1") (pinfunction "-Vin_1") (pintype "passive"))
      (node (ref "U9") (pin "5") (pinfunction "GND_5") (pintype "passive"))
      (node (ref "VD1") (pin "3") (pinfunction "Emitter_3") (pintype "passive"))
      (node (ref "VD10") (pin "3") (pinfunction "Emitter_3") (pintype "passive"))
      (node (ref "VD11") (pin "3") (pinfunction "Emitter_3") (pintype "passive"))
      (node (ref "VD2") (pin "3") (pinfunction "Emitter_3") (pintype "passive"))
      (node (ref "VD3") (pin "3") (pinfunction "Emitter_3") (pintype "passive"))
      (node (ref "VD4") (pin "3") (pinfunction "Emitter_3") (pintype "passive"))
      (node (ref "VD5") (pin "3") (pinfunction "Emitter_3") (pintype "passive"))
      (node (ref "VD6") (pin "3") (pinfunction "Emitter_3") (pintype "passive"))
      (node (ref "VD7") (pin "3") (pinfunction "Emitter_3") (pintype "passive"))
      (node (ref "VD8") (pin "3") (pinfunction "Emitter_3") (pintype "passive"))
      (node (ref "VD9") (pin "3") (pinfunction "Emitter_3") (pintype "passive"))
      (node (ref "X1") (pin "2") (pinfunction "GND_2") (pintype "passive"))
      (node (ref "X1") (pin "4") (pinfunction "GND_4") (pintype "passive"))
      (node (ref "X2") (pin "2") (pinfunction "2_2") (pintype "passive"))
      (node (ref "X2") (pin "3") (pinfunction "3_3") (pintype "passive"))
      (node (ref "X3") (pin "2") (pinfunction "GND_2") (pintype "passive"))
      (node (ref "X3") (pin "4") (pinfunction "GND_4") (pintype "passive"))
    )
    (net (code "56") (name "LGND") (class "Default")
      (node (ref "J9") (pin "3") (pinfunction "3_3") (pintype "passive"))
      (node (ref "VD1") (pin "2") (pinfunction "Cathode_/_Anode_2") (pintype "passive"))
      (node (ref "VD10") (pin "2") (pinfunction "Cathode_/_Anode_2") (pintype "passive"))
      (node (ref "VD11") (pin "2") (pinfunction "Cathode_/_Anode_2") (pintype "passive"))
      (node (ref "VD2") (pin "2") (pinfunction "Cathode_/_Anode_2") (pintype "passive"))
      (node (ref "VD3") (pin "2") (pinfunction "Cathode_/_Anode_2") (pintype "passive"))
      (node (ref "VD4") (pin "2") (pinfunction "Cathode_/_Anode_2") (pintype "passive"))
      (node (ref "VD5") (pin "2") (pinfunction "Cathode_/_Anode_2") (pintype "passive"))
      (node (ref "VD6") (pin "2") (pinfunction "Cathode_/_Anode_2") (pintype "passive"))
      (node (ref "VD7") (pin "2") (pinfunction "Cathode_/_Anode_2") (pintype "passive"))
      (node (ref "VD8") (pin "2") (pinfunction "Cathode_/_Anode_2") (pintype "passive"))
      (node (ref "VD9") (pin "2") (pinfunction "Cathode_/_Anode_2") (pintype "passive"))
    )
    (net (code "57") (name "Net-(C1-Pad2)") (class "Default")
      (node (ref "C1") (pin "2") (pinfunction "2_2") (pintype "passive"))
      (node (ref "J2") (pin "1") (pinfunction "1_1") (pintype "passive"))
      (node (ref "R7") (pin "2") (pinfunction "2_2") (pintype "passive"))
      (node (ref "R8") (pin "1") (pinfunction "1_1") (pintype "passive"))
    )
    (net (code "58") (name "Net-(C18-Pad2)") (class "Default")
      (node (ref "C18") (pin "2") (pinfunction "2_2") (pintype "passive"))
      (node (ref "R32") (pin "2") (pinfunction "2_2") (pintype "passive"))
      (node (ref "R33") (pin "1") (pinfunction "1_1") (pintype "passive"))
    )
    (net (code "59") (name "Net-(D4-+)") (class "Default")
      (node (ref "D4") (pin "1") (pinfunction "+_1") (pintype "passive"))
      (node (ref "Q2") (pin "3") (pinfunction "SOURCE_3") (pintype "passive"))
      (node (ref "R35") (pin "1") (pinfunction "1_1") (pintype "passive"))
      (node (ref "U3") (pin "9") (pinfunction "OUT_9") (pintype "passive"))
      (node (ref "U6") (pin "1") (pinfunction "IN-_1") (pintype "passive"))
    )
    (net (code "60") (name "Net-(D5-K)") (class "Default")
      (node (ref "D5") (pin "2") (pinfunction "K_2") (pintype "passive"))
      (node (ref "R43") (pin "1") (pinfunction "1_1") (pintype "passive"))
    )
    (net (code "61") (name "Net-(D6-K)") (class "Default")
      (node (ref "D6") (pin "2") (pinfunction "K_2") (pintype "passive"))
      (node (ref "R44") (pin "1") (pinfunction "1_1") (pintype "passive"))
    )
    (net (code "62") (name "Net-(J3-Pad2)") (class "Default")
      (node (ref "J3") (pin "2") (pinfunction "2_2") (pintype "passive"))
      (node (ref "R4") (pin "2") (pinfunction "2_2") (pintype "passive"))
    )
    (net (code "63") (name "Net-(J3-Pad3)") (class "Default")
      (node (ref "J3") (pin "3") (pinfunction "3_3") (pintype "passive"))
      (node (ref "R3") (pin "2") (pinfunction "2_2") (pintype "passive"))
    )
    (net (code "64") (name "Net-(J7-Pad10)") (class "Default")
      (node (ref "J7") (pin "10") (pinfunction "10_10") (pintype "passive"))
      (node (ref "R40") (pin "2") (pinfunction "2_2") (pintype "passive"))
    )
    (net (code "65") (name "Net-(J7-Pad11)") (class "Default")
      (node (ref "J7") (pin "11") (pinfunction "11_11") (pintype "passive"))
      (node (ref "R37") (pin "2") (pinfunction "2_2") (pintype "passive"))
    )
    (net (code "66") (name "Net-(J7-RD+)") (class "Default")
      (node (ref "J7") (pin "3") (pinfunction "RD+_3") (pintype "passive"))
      (node (ref "R27") (pin "1") (pinfunction "1_1") (pintype "passive"))
      (node (ref "U1") (pin "23") (pinfunction "RXP_23") (pintype "passive"))
    )
    (net (code "67") (name "Net-(J7-RD-)") (class "Default")
      (node (ref "J7") (pin "6") (pinfunction "RD-_6") (pintype "passive"))
      (node (ref "R29") (pin "1") (pinfunction "1_1") (pintype "passive"))
      (node (ref "U1") (pin "22") (pinfunction "RXN_22") (pintype "passive"))
    )
    (net (code "68") (name "Net-(J7-TD+)") (class "Default")
      (node (ref "J7") (pin "1") (pinfunction "TD+_1") (pintype "passive"))
      (node (ref "R23") (pin "1") (pinfunction "1_1") (pintype "passive"))
      (node (ref "U1") (pin "21") (pinfunction "TXP_21") (pintype "passive"))
    )
    (net (code "69") (name "Net-(J7-TD-)") (class "Default")
      (node (ref "J7") (pin "2") (pinfunction "TD-_2") (pintype "passive"))
      (node (ref "R24") (pin "1") (pinfunction "1_1") (pintype "passive"))
      (node (ref "U1") (pin "20") (pinfunction "TXN_20") (pintype "passive"))
    )
    (net (code "70") (name "Net-(J9-Pad1)") (class "Default")
      (node (ref "J9") (pin "1") (pinfunction "1_1") (pintype "passive"))
      (node (ref "R49") (pin "1") (pinfunction "1_1") (pintype "passive"))
    )
    (net (code "71") (name "Net-(J9-Pad2)") (class "Default")
      (node (ref "J9") (pin "2") (pinfunction "2_2") (pintype "passive"))
      (node (ref "R48") (pin "1") (pinfunction "1_1") (pintype "passive"))
    )
    (net (code "72") (name "Net-(J10-Pad1)") (class "Default")
      (node (ref "J10") (pin "1") (pinfunction "1_1") (pintype "passive"))
      (node (ref "R50") (pin "1") (pinfunction "1_1") (pintype "passive"))
    )
    (net (code "73") (name "Net-(J10-Pad2)") (class "Default")
      (node (ref "J10") (pin "2") (pinfunction "2_2") (pintype "passive"))
      (node (ref "R51") (pin "1") (pinfunction "1_1") (pintype "passive"))
    )
    (net (code "74") (name "Net-(J11-Pad1)") (class "Default")
      (node (ref "J11") (pin "1") (pinfunction "1_1") (pintype "passive"))
      (node (ref "R52") (pin "1") (pinfunction "1_1") (pintype "passive"))
    )
    (net (code "75") (name "Net-(J11-Pad2)") (class "Default")
      (node (ref "J11") (pin "2") (pinfunction "2_2") (pintype "passive"))
      (node (ref "R53") (pin "1") (pinfunction "1_1") (pintype "passive"))
    )
    (net (code "76") (name "Net-(J12-Pad1)") (class "Default")
      (node (ref "J12") (pin "1") (pinfunction "1_1") (pintype "passive"))
      (node (ref "R54") (pin "1") (pinfunction "1_1") (pintype "passive"))
    )
    (net (code "77") (name "Net-(J12-Pad2)") (class "Default")
      (node (ref "J12") (pin "2") (pinfunction "2_2") (pintype "passive"))
      (node (ref "R55") (pin "1") (pinfunction "1_1") (pintype "passive"))
    )
    (net (code "78") (name "Net-(J13-Pad1)") (class "Default")
      (node (ref "J13") (pin "1") (pinfunction "1_1") (pintype "passive"))
      (node (ref "R58") (pin "1") (pinfunction "1_1") (pintype "passive"))
    )
    (net (code "79") (name "Net-(J13-Pad2)") (class "Default")
      (node (ref "J13") (pin "2") (pinfunction "2_2") (pintype "passive"))
      (node (ref "R57") (pin "1") (pinfunction "1_1") (pintype "passive"))
    )
    (net (code "80") (name "Net-(J13-Pad3)") (class "Default")
      (node (ref "J13") (pin "3") (pinfunction "3_3") (pintype "passive"))
      (node (ref "R56") (pin "1") (pinfunction "1_1") (pintype "passive"))
    )
    (net (code "81") (name "Net-(Q1-B)") (class "Default")
      (node (ref "Q1") (pin "1") (pinfunction "B_1") (pintype "passive"))
      (node (ref "R16") (pin "2") (pinfunction "2_2") (pintype "passive"))
    )
    (net (code "82") (name "Net-(Q1-C)") (class "Default")
      (node (ref "Q1") (pin "3") (pinfunction "C_3") (pintype "passive"))
      (node (ref "R15") (pin "2") (pinfunction "2_2") (pintype "passive"))
      (node (ref "R4") (pin "1") (pinfunction "1_1") (pintype "passive"))
    )
    (net (code "83") (name "Net-(Q2-DRAIN)") (class "Default")
      (node (ref "Q2") (pin "2") (pinfunction "DRAIN_2") (pintype "passive"))
      (node (ref "R28") (pin "1") (pinfunction "1_1") (pintype "passive"))
      (node (ref "R30") (pin "1") (pinfunction "1_1") (pintype "passive"))
      (node (ref "U3") (pin "1") (pinfunction "SENSE_1") (pintype "passive"))
    )
    (net (code "84") (name "Net-(Q2-GATE)") (class "Default")
      (node (ref "Q2") (pin "1") (pinfunction "GATE_1") (pintype "passive"))
      (node (ref "U3") (pin "10") (pinfunction "GATE_10") (pintype "passive"))
    )
    (net (code "85") (name "Net-(R10-Pad1)") (class "Default")
      (node (ref "R10") (pin "1") (pinfunction "1_1") (pintype "passive"))
      (node (ref "R11") (pin "1") (pinfunction "1_1") (pintype "passive"))
      (node (ref "R9") (pin "2") (pinfunction "2_2") (pintype "passive"))
    )
    (net (code "86") (name "Net-(R22-Pad2)") (class "Default")
      (node (ref "R22") (pin "2") (pinfunction "2_2") (pintype "passive"))
      (node (ref "SW1") (pin "1") (pinfunction "1_1") (pintype "passive"))
      (node (ref "SW1") (pin "2") (pinfunction "2_2") (pintype "passive"))
    )
    (net (code "87") (name "Net-(R47-Pad1)") (class "Default")
      (node (ref "R47") (pin "1") (pinfunction "1_1") (pintype "passive"))
      (node (ref "TP1") (pin "1") (pinfunction "1_1") (pintype "passive"))
    )
    (net (code "88") (name "Net-(R48-Pad2)") (class "Default")
      (node (ref "R48") (pin "2") (pinfunction "2_2") (pintype "passive"))
      (node (ref "R60") (pin "1") (pinfunction "1_1") (pintype "passive"))
    )
    (net (code "89") (name "Net-(R49-Pad2)") (class "Default")
      (node (ref "R49") (pin "2") (pinfunction "2_2") (pintype "passive"))
      (node (ref "R61") (pin "1") (pinfunction "1_1") (pintype "passive"))
    )
    (net (code "90") (name "Net-(R50-Pad2)") (class "Default")
      (node (ref "R50") (pin "2") (pinfunction "2_2") (pintype "passive"))
      (node (ref "R62") (pin "1") (pinfunction "1_1") (pintype "passive"))
    )
    (net (code "91") (name "Net-(R51-Pad2)") (class "Default")
      (node (ref "R51") (pin "2") (pinfunction "2_2") (pintype "passive"))
      (node (ref "R63") (pin "1") (pinfunction "1_1") (pintype "passive"))
    )
    (net (code "92") (name "Net-(R52-Pad2)") (class "Default")
      (node (ref "R52") (pin "2") (pinfunction "2_2") (pintype "passive"))
      (node (ref "R64") (pin "1") (pinfunction "1_1") (pintype "passive"))
    )
    (net (code "93") (name "Net-(R53-Pad2)") (class "Default")
      (node (ref "R53") (pin "2") (pinfunction "2_2") (pintype "passive"))
      (node (ref "R65") (pin "1") (pinfunction "1_1") (pintype "passive"))
    )
    (net (code "94") (name "Net-(R54-Pad2)") (class "Default")
      (node (ref "R54") (pin "2") (pinfunction "2_2") (pintype "passive"))
      (node (ref "R66") (pin "1") (pinfunction "1_1") (pintype "passive"))
    )
    (net (code "95") (name "Net-(R55-Pad2)") (class "Default")
      (node (ref "R55") (pin "2") (pinfunction "2_2") (pintype "passive"))
      (node (ref "R67") (pin "1") (pinfunction "1_1") (pintype "passive"))
    )
    (net (code "96") (name "Net-(R56-Pad2)") (class "Default")
      (node (ref "R56") (pin "2") (pinfunction "2_2") (pintype "passive"))
      (node (ref "R68") (pin "1") (pinfunction "1_1") (pintype "passive"))
    )
    (net (code "97") (name "Net-(R57-Pad2)") (class "Default")
      (node (ref "R57") (pin "2") (pinfunction "2_2") (pintype "passive"))
      (node (ref "R69") (pin "1") (pinfunction "1_1") (pintype "passive"))
    )
    (net (code "98") (name "Net-(R58-Pad2)") (class "Default")
      (node (ref "R58") (pin "2") (pinfunction "2_2") (pintype "passive"))
      (node (ref "R70") (pin "1") (pinfunction "1_1") (pintype "passive"))
    )
    (net (code "99") (name "Net-(U1-LED1{slash}REGOFF)") (class "Default")
      (node (ref "J7") (pin "9") (pinfunction "9_9") (pintype "passive"))
      (node (ref "U1") (pin "3") (pinfunction "LED1/REGOFF_3") (pintype "passive"))
    )
    (net (code "100") (name "Net-(U1-LED2{slash}nINTSEL)") (class "Default")
      (node (ref "J7") (pin "12") (pinfunction "12_12") (pintype "passive"))
      (node (ref "R36") (pin "2") (pinfunction "2_2") (pintype "passive"))
      (node (ref "U1") (pin "2") (pinfunction "LED2/nINTSEL_2") (pintype "passive"))
    )
    (net (code "101") (name "Net-(U1-RBIAS)") (class "Default")
      (node (ref "R25") (pin "2") (pinfunction "2_2") (pintype "passive"))
      (node (ref "U1") (pin "24") (pinfunction "RBIAS_24") (pintype "passive"))
    )
    (net (code "102") (name "Net-(U1-RXER{slash}PHYAD0)") (class "Default")
      (node (ref "R6") (pin "2") (pinfunction "2_2") (pintype "passive"))
      (node (ref "U1") (pin "10") (pinfunction "RXER/PHYAD0_10") (pintype "passive"))
    )
    (net (code "103") (name "Net-(U1-VDD1A)") (class "Default")
      (node (ref "C10") (pin "2") (pinfunction "2_2") (pintype "passive"))
      (node (ref "C16") (pin "2") (pinfunction "2_2") (pintype "passive"))
      (node (ref "C17") (pin "2") (pinfunction "2_2") (pintype "passive"))
      (node (ref "C20") (pin "2") (pinfunction "2_2") (pintype "passive"))
      (node (ref "J7") (pin "4") (pinfunction "4_4") (pintype "passive"))
      (node (ref "J7") (pin "5") (pinfunction "5_5") (pintype "passive"))
      (node (ref "L1") (pin "1") (pinfunction "1_1") (pintype "passive"))
      (node (ref "R23") (pin "2") (pinfunction "2_2") (pintype "passive"))
      (node (ref "R24") (pin "2") (pinfunction "2_2") (pintype "passive"))
      (node (ref "R27") (pin "2") (pinfunction "2_2") (pintype "passive"))
      (node (ref "R29") (pin "2") (pinfunction "2_2") (pintype "passive"))
      (node (ref "U1") (pin "1") (pinfunction "VDD2A_1") (pintype "passive"))
      (node (ref "U1") (pin "19") (pinfunction "VDD1A_19") (pintype "passive"))
    )
    (net (code "104") (name "Net-(U1-VDDCR)") (class "Default")
      (node (ref "C12") (pin "2") (pinfunction "2_2") (pintype "passive"))
      (node (ref "U1") (pin "6") (pinfunction "VDDCR_6") (pintype "passive"))
    )
    (net (code "105") (name "Net-(U1-XTAL1{slash}CLKIN)") (class "Default")
      (node (ref "C2") (pin "2") (pinfunction "2_2") (pintype "passive"))
      (node (ref "U1") (pin "5") (pinfunction "XTAL1/CLKIN_5") (pintype "passive"))
      (node (ref "X1") (pin "3") (pinfunction "X2_3") (pintype "passive"))
    )
    (net (code "106") (name "Net-(U1-XTAL2)") (class "Default")
      (node (ref "C3") (pin "2") (pinfunction "2_2") (pintype "passive"))
      (node (ref "U1") (pin "4") (pinfunction "XTAL2_4") (pintype "passive"))
      (node (ref "X1") (pin "1") (pinfunction "X1_1") (pintype "passive"))
    )
    (net (code "107") (name "Net-(U2-+IN)") (class "Default")
      (node (ref "R11") (pin "2") (pinfunction "2_2") (pintype "passive"))
      (node (ref "R8") (pin "2") (pinfunction "2_2") (pintype "passive"))
      (node (ref "U2") (pin "3") (pinfunction "+IN_3") (pintype "passive"))
    )
    (net (code "108") (name "Net-(U2--IN)") (class "Default")
      (node (ref "R17") (pin "1") (pinfunction "1_1") (pintype "passive"))
      (node (ref "R19") (pin "1") (pinfunction "1_1") (pintype "passive"))
      (node (ref "U2") (pin "4") (pinfunction "-IN_4") (pintype "passive"))
    )
    (net (code "109") (name "Net-(U3-OVLO)") (class "Default")
      (node (ref "R13") (pin "2") (pinfunction "2_2") (pintype "passive"))
      (node (ref "R14") (pin "2") (pinfunction "2_2") (pintype "passive"))
      (node (ref "U3") (pin "4") (pinfunction "OVLO_4") (pintype "passive"))
    )
    (net (code "110") (name "Net-(U3-PWR)") (class "Default")
      (node (ref "R18") (pin "1") (pinfunction "1_1") (pintype "passive"))
      (node (ref "U3") (pin "7") (pinfunction "PWR_7") (pintype "passive"))
    )
    (net (code "111") (name "Net-(U3-TIMER)") (class "Default")
      (node (ref "C4") (pin "2") (pinfunction "2_2") (pintype "passive"))
      (node (ref "C5") (pin "2") (pinfunction "2_2") (pintype "passive"))
      (node (ref "U3") (pin "6") (pinfunction "TIMER_6") (pintype "passive"))
    )
    (net (code "112") (name "Net-(U4-BOOT)") (class "Default")
      (node (ref "C14") (pin "1") (pinfunction "1_1") (pintype "passive"))
      (node (ref "U4") (pin "6") (pinfunction "BOOT_6") (pintype "passive"))
    )
    (net (code "113") (name "Net-(U4-EN)") (class "Default")
      (node (ref "R20") (pin "2") (pinfunction "2_2") (pintype "passive"))
      (node (ref "R21") (pin "1") (pinfunction "1_1") (pintype "passive"))
      (node (ref "U4") (pin "5") (pinfunction "EN_5") (pintype "passive"))
    )
    (net (code "114") (name "Net-(U4-FB)") (class "Default")
      (node (ref "C18") (pin "1") (pinfunction "1_1") (pintype "passive"))
      (node (ref "R31") (pin "1") (pinfunction "1_1") (pintype "passive"))
      (node (ref "R33") (pin "2") (pinfunction "2_2") (pintype "passive"))
      (node (ref "R34") (pin "1") (pinfunction "1_1") (pintype "passive"))
      (node (ref "U4") (pin "4") (pinfunction "FB_4") (pintype "passive"))
    )
    (net (code "115") (name "Net-(U4-SW)") (class "Default")
      (node (ref "C14") (pin "2") (pinfunction "2_2") (pintype "passive"))
      (node (ref "L2") (pin "1") (pinfunction "1_1") (pintype "passive"))
      (node (ref "U4") (pin "2") (pinfunction "SW_2") (pintype "passive"))
    )
    (net (code "116") (name "Net-(U5-BST)") (class "Default")
      (node (ref "C13") (pin "1") (pinfunction "1_1") (pintype "passive"))
      (node (ref "U5") (pin "6") (pinfunction "BST_6") (pintype "passive"))
    )
    (net (code "117") (name "Net-(U5-SW)") (class "Default")
      (node (ref "C13") (pin "2") (pinfunction "2_2") (pintype "passive"))
      (node (ref "L3") (pin "1") (pinfunction "1_1") (pintype "passive"))
      (node (ref "U5") (pin "5") (pinfunction "SW_5") (pintype "passive"))
    )
    (net (code "118") (name "Net-(U6-OUT)") (class "Default")
      (node (ref "R46") (pin "1") (pinfunction "1_1") (pintype "passive"))
      (node (ref "U6") (pin "5") (pinfunction "OUT_5") (pintype "passive"))
    )
    (net (code "119") (name "Net-(U11-PA8)") (class "Default")
      (node (ref "TP2") (pin "1") (pinfunction "1_1") (pintype "passive"))
      (node (ref "U11") (pin "67") (pinfunction "PA8_67") (pintype "passive"))
    )
    (net (code "120") (name "Net-(U11-PA9)") (class "Default")
      (node (ref "TP3") (pin "1") (pinfunction "1_1") (pintype "passive"))
      (node (ref "U11") (pin "68") (pinfunction "PA9_68") (pintype "passive"))
    )
    (net (code "121") (name "Net-(U11-PA10)") (class "Default")
      (node (ref "TP4") (pin "1") (pinfunction "1_1") (pintype "passive"))
      (node (ref "U11") (pin "69") (pinfunction "PA10_69") (pintype "passive"))
    )
    (net (code "122") (name "Net-(U11-PA15(JTDI))") (class "Default")
      (node (ref "TP5") (pin "1") (pinfunction "1_1") (pintype "passive"))
      (node (ref "U11") (pin "77") (pinfunction "PA15(JTDI)_77") (pintype "passive"))
    )
    (net (code "123") (name "Net-(U11-PB0)") (class "Default")
      (node (ref "TP18") (pin "1") (pinfunction "1_1") (pintype "passive"))
      (node (ref "U11") (pin "35") (pinfunction "PB0_35") (pintype "passive"))
    )
    (net (code "124") (name "Net-(U11-PB1)") (class "Default")
      (node (ref "TP19") (pin "1") (pinfunction "1_1") (pintype "passive"))
      (node (ref "U11") (pin "36") (pinfunction "PB1_36") (pintype "passive"))
    )
    (net (code "125") (name "Net-(U11-PB2-BOOT1(PB2))") (class "Default")
      (node (ref "TP20") (pin "1") (pinfunction "1_1") (pintype "passive"))
      (node (ref "U11") (pin "37") (pinfunction "PB2-BOOT1(PB2)_37") (pintype "passive"))
    )
    (net (code "126") (name "Net-(U11-PB3(JTDOTRACESWO))") (class "Default")
      (node (ref "TP21") (pin "1") (pinfunction "1_1") (pintype "passive"))
      (node (ref "U11") (pin "89") (pinfunction "PB3(JTDOTRACESWO)_89") (pintype "passive"))
    )
    (net (code "127") (name "Net-(U11-PC6)") (class "Default")
      (node (ref "TP6") (pin "1") (pinfunction "1_1") (pintype "passive"))
      (node (ref "U11") (pin "63") (pinfunction "PC6_63") (pintype "passive"))
    )
    (net (code "128") (name "Net-(U11-PC7)") (class "Default")
      (node (ref "TP7") (pin "1") (pinfunction "1_1") (pintype "passive"))
      (node (ref "U11") (pin "64") (pinfunction "PC7_64") (pintype "passive"))
    )
    (net (code "129") (name "Net-(U11-PC8)") (class "Default")
      (node (ref "TP8") (pin "1") (pinfunction "1_1") (pintype "passive"))
      (node (ref "U11") (pin "65") (pinfunction "PC8_65") (pintype "passive"))
    )
    (net (code "130") (name "Net-(U11-PC9)") (class "Default")
      (node (ref "TP9") (pin "1") (pinfunction "1_1") (pintype "passive"))
      (node (ref "U11") (pin "66") (pinfunction "PC9_66") (pintype "passive"))
    )
    (net (code "131") (name "Net-(U11-PC12)") (class "Default")
      (node (ref "TP10") (pin "1") (pinfunction "1_1") (pintype "passive"))
      (node (ref "U11") (pin "80") (pinfunction "PC12_80") (pintype "passive"))
    )
    (net (code "132") (name "Net-(U11-PC13)") (class "Default")
      (node (ref "TP11") (pin "1") (pinfunction "1_1") (pintype "passive"))
      (node (ref "U11") (pin "7") (pinfunction "PC13_7") (pintype "passive"))
    )
    (net (code "133") (name "Net-(U11-PC14-OSC32_IN(PC14))") (class "Default")
      (node (ref "C32") (pin "2") (pinfunction "2_2") (pintype "passive"))
      (node (ref "U11") (pin "8") (pinfunction "PC14-OSC32_IN(PC14)_8") (pintype "passive"))
      (node (ref "X2") (pin "4") (pinfunction "OSC2_4") (pintype "passive"))
    )
    (net (code "134") (name "Net-(U11-PC15-OSC32_OUT(PC15))") (class "Default")
      (node (ref "C38") (pin "2") (pinfunction "2_2") (pintype "passive"))
      (node (ref "U11") (pin "9") (pinfunction "PC15-OSC32_OUT(PC15)_9") (pintype "passive"))
      (node (ref "X2") (pin "1") (pinfunction "OSC1_1") (pintype "passive"))
    )
    (net (code "135") (name "Net-(U11-PD0)") (class "Default")
      (node (ref "TP22") (pin "1") (pinfunction "1_1") (pintype "passive"))
      (node (ref "U11") (pin "81") (pinfunction "PD0_81") (pintype "passive"))
    )
    (net (code "136") (name "Net-(U11-PD1)") (class "Default")
      (node (ref "TP23") (pin "1") (pinfunction "1_1") (pintype "passive"))
      (node (ref "U11") (pin "82") (pinfunction "PD1_82") (pintype "passive"))
    )
    (net (code "137") (name "Net-(U11-PD2)") (class "Default")
      (node (ref "TP24") (pin "1") (pinfunction "1_1") (pintype "passive"))
      (node (ref "U11") (pin "83") (pinfunction "PD2_83") (pintype "passive"))
    )
    (net (code "138") (name "Net-(U11-PD3)") (class "Default")
      (node (ref "TP25") (pin "1") (pinfunction "1_1") (pintype "passive"))
      (node (ref "U11") (pin "84") (pinfunction "PD3_84") (pintype "passive"))
    )
    (net (code "139") (name "Net-(U11-PD4)") (class "Default")
      (node (ref "TP26") (pin "1") (pinfunction "1_1") (pintype "passive"))
      (node (ref "U11") (pin "85") (pinfunction "PD4_85") (pintype "passive"))
    )
    (net (code "140") (name "Net-(U11-PD5)") (class "Default")
      (node (ref "TP27") (pin "1") (pinfunction "1_1") (pintype "passive"))
      (node (ref "U11") (pin "86") (pinfunction "PD5_86") (pintype "passive"))
    )
    (net (code "141") (name "Net-(U11-PD6)") (class "Default")
      (node (ref "TP28") (pin "1") (pinfunction "1_1") (pintype "passive"))
      (node (ref "U11") (pin "87") (pinfunction "PD6_87") (pintype "passive"))
    )
    (net (code "142") (name "Net-(U11-PD7)") (class "Default")
      (node (ref "TP29") (pin "1") (pinfunction "1_1") (pintype "passive"))
      (node (ref "U11") (pin "88") (pinfunction "PD7_88") (pintype "passive"))
    )
    (net (code "143") (name "Net-(U11-PD9)") (class "Default")
      (node (ref "TP30") (pin "1") (pinfunction "1_1") (pintype "passive"))
      (node (ref "U11") (pin "56") (pinfunction "PD9_56") (pintype "passive"))
    )
    (net (code "144") (name "Net-(U11-PD10)") (class "Default")
      (node (ref "TP31") (pin "1") (pinfunction "1_1") (pintype "passive"))
      (node (ref "U11") (pin "57") (pinfunction "PD10_57") (pintype "passive"))
    )
    (net (code "145") (name "Net-(U11-PD11)") (class "Default")
      (node (ref "TP32") (pin "1") (pinfunction "1_1") (pintype "passive"))
      (node (ref "U11") (pin "58") (pinfunction "PD11_58") (pintype "passive"))
    )
    (net (code "146") (name "Net-(U11-PD12)") (class "Default")
      (node (ref "TP33") (pin "1") (pinfunction "1_1") (pintype "passive"))
      (node (ref "U11") (pin "59") (pinfunction "PD12_59") (pintype "passive"))
    )
    (net (code "147") (name "Net-(U11-PD13)") (class "Default")
      (node (ref "TP34") (pin "1") (pinfunction "1_1") (pintype "passive"))
      (node (ref "U11") (pin "60") (pinfunction "PD13_60") (pintype "passive"))
    )
    (net (code "148") (name "Net-(U11-PD14)") (class "Default")
      (node (ref "TP35") (pin "1") (pinfunction "1_1") (pintype "passive"))
      (node (ref "U11") (pin "61") (pinfunction "PD14_61") (pintype "passive"))
    )
    (net (code "149") (name "Net-(U11-PD15)") (class "Default")
      (node (ref "TP36") (pin "1") (pinfunction "1_1") (pintype "passive"))
      (node (ref "U11") (pin "62") (pinfunction "PD15_62") (pintype "passive"))
    )
    (net (code "150") (name "Net-(U11-PE7)") (class "Default")
      (node (ref "TP12") (pin "1") (pinfunction "1_1") (pintype "passive"))
      (node (ref "U11") (pin "38") (pinfunction "PE7_38") (pintype "passive"))
    )
    (net (code "151") (name "Net-(U11-PE8)") (class "Default")
      (node (ref "TP13") (pin "1") (pinfunction "1_1") (pintype "passive"))
      (node (ref "U11") (pin "39") (pinfunction "PE8_39") (pintype "passive"))
    )
    (net (code "152") (name "Net-(U11-PE9)") (class "Default")
      (node (ref "TP14") (pin "1") (pinfunction "1_1") (pintype "passive"))
      (node (ref "U11") (pin "40") (pinfunction "PE9_40") (pintype "passive"))
    )
    (net (code "153") (name "Net-(U11-PE10)") (class "Default")
      (node (ref "TP15") (pin "1") (pinfunction "1_1") (pintype "passive"))
      (node (ref "U11") (pin "41") (pinfunction "PE10_41") (pintype "passive"))
    )
    (net (code "154") (name "Net-(U11-PE11)") (class "Default")
      (node (ref "TP16") (pin "1") (pinfunction "1_1") (pintype "passive"))
      (node (ref "U11") (pin "42") (pinfunction "PE11_42") (pintype "passive"))
    )
    (net (code "155") (name "Net-(U11-PE12)") (class "Default")
      (node (ref "TP17") (pin "1") (pinfunction "1_1") (pintype "passive"))
      (node (ref "U11") (pin "43") (pinfunction "PE12_43") (pintype "passive"))
    )
    (net (code "156") (name "Net-(U11-PH0-OSC_IN(PH0))") (class "Default")
      (node (ref "C53") (pin "2") (pinfunction "2_2") (pintype "passive"))
      (node (ref "U11") (pin "12") (pinfunction "PH0-OSC_IN(PH0)_12") (pintype "passive"))
      (node (ref "X3") (pin "3") (pinfunction "X2_3") (pintype "passive"))
    )
    (net (code "157") (name "Net-(U11-PH1-OSC_OUT(PH1))") (class "Default")
      (node (ref "C47") (pin "2") (pinfunction "2_2") (pintype "passive"))
      (node (ref "U11") (pin "13") (pinfunction "PH1-OSC_OUT(PH1)_13") (pintype "passive"))
      (node (ref "X3") (pin "1") (pinfunction "X1_1") (pintype "passive"))
    )
    (net (code "158") (name "Net-(U11-VBAT)") (class "Default")
      (node (ref "B1") (pin "1") (pinfunction "1_1") (pintype "passive"))
      (node (ref "C33") (pin "2") (pinfunction "2_2") (pintype "passive"))
      (node (ref "U11") (pin "6") (pinfunction "VBAT_6") (pintype "passive"))
    )
    (net (code "159") (name "Net-(U11-VCAP_1)") (class "Default")
      (node (ref "C52") (pin "2") (pinfunction "2_2") (pintype "passive"))
      (node (ref "U11") (pin "49") (pinfunction "VCAP_1_49") (pintype "passive"))
    )
    (net (code "160") (name "Net-(U11-VCAP_2)") (class "Default")
      (node (ref "C50") (pin "2") (pinfunction "2_2") (pintype "passive"))
      (node (ref "U11") (pin "73") (pinfunction "VCAP_2_73") (pintype "passive"))
    )
    (net (code "161") (name "Net-(U11-VDA)") (class "Default")
      (node (ref "C49") (pin "2") (pinfunction "2_2") (pintype "passive"))
      (node (ref "C51") (pin "2") (pinfunction "2_2") (pintype "passive"))
      (node (ref "L4") (pin "2") (pinfunction "2_2") (pintype "passive"))
      (node (ref "U11") (pin "22") (pinfunction "VDA_22") (pintype "passive"))
    )
    (net (code "162") (name "Net-(VD1-Anode_{slash}_Cathode)") (class "Default")
      (node (ref "R60") (pin "2") (pinfunction "2_2") (pintype "passive"))
      (node (ref "VD1") (pin "1") (pinfunction "Anode_/_Cathode_1") (pintype "passive"))
    )
    (net (code "163") (name "Net-(VD1-Collector)") (class "Default")
      (node (ref "R73") (pin "2") (pinfunction "2_2") (pintype "passive"))
      (node (ref "R84") (pin "1") (pinfunction "1_1") (pintype "passive"))
      (node (ref "VD1") (pin "4") (pinfunction "Collector_4") (pintype "passive"))
    )
    (net (code "164") (name "Net-(VD2-Anode_{slash}_Cathode)") (class "Default")
      (node (ref "R61") (pin "2") (pinfunction "2_2") (pintype "passive"))
      (node (ref "VD2") (pin "1") (pinfunction "Anode_/_Cathode_1") (pintype "passive"))
    )
    (net (code "165") (name "Net-(VD2-Collector)") (class "Default")
      (node (ref "R74") (pin "2") (pinfunction "2_2") (pintype "passive"))
      (node (ref "R85") (pin "1") (pinfunction "1_1") (pintype "passive"))
      (node (ref "VD2") (pin "4") (pinfunction "Collector_4") (pintype "passive"))
    )
    (net (code "166") (name "Net-(VD3-Anode_{slash}_Cathode)") (class "Default")
      (node (ref "R62") (pin "2") (pinfunction "2_2") (pintype "passive"))
      (node (ref "VD3") (pin "1") (pinfunction "Anode_/_Cathode_1") (pintype "passive"))
    )
    (net (code "167") (name "Net-(VD3-Collector)") (class "Default")
      (node (ref "R75") (pin "2") (pinfunction "2_2") (pintype "passive"))
      (node (ref "R86") (pin "1") (pinfunction "1_1") (pintype "passive"))
      (node (ref "VD3") (pin "4") (pinfunction "Collector_4") (pintype "passive"))
    )
    (net (code "168") (name "Net-(VD4-Anode_{slash}_Cathode)") (class "Default")
      (node (ref "R63") (pin "2") (pinfunction "2_2") (pintype "passive"))
      (node (ref "VD4") (pin "1") (pinfunction "Anode_/_Cathode_1") (pintype "passive"))
    )
    (net (code "169") (name "Net-(VD5-Anode_{slash}_Cathode)") (class "Default")
      (node (ref "R64") (pin "2") (pinfunction "2_2") (pintype "passive"))
      (node (ref "VD5") (pin "1") (pinfunction "Anode_/_Cathode_1") (pintype "passive"))
    )
    (net (code "170") (name "Net-(VD6-Anode_{slash}_Cathode)") (class "Default")
      (node (ref "R65") (pin "2") (pinfunction "2_2") (pintype "passive"))
      (node (ref "VD6") (pin "1") (pinfunction "Anode_/_Cathode_1") (pintype "passive"))
    )
    (net (code "171") (name "Net-(VD7-Anode_{slash}_Cathode)") (class "Default")
      (node (ref "R66") (pin "2") (pinfunction "2_2") (pintype "passive"))
      (node (ref "VD7") (pin "1") (pinfunction "Anode_/_Cathode_1") (pintype "passive"))
    )
    (net (code "172") (name "Net-(VD8-Anode_{slash}_Cathode)") (class "Default")
      (node (ref "R67") (pin "2") (pinfunction "2_2") (pintype "passive"))
      (node (ref "VD8") (pin "1") (pinfunction "Anode_/_Cathode_1") (pintype "passive"))
    )
    (net (code "173") (name "Net-(VD9-Anode_{slash}_Cathode)") (class "Default")
      (node (ref "R68") (pin "2") (pinfunction "2_2") (pintype "passive"))
      (node (ref "VD9") (pin "1") (pinfunction "Anode_/_Cathode_1") (pintype "passive"))
    )
    (net (code "174") (name "Net-(VD10-Anode_{slash}_Cathode)") (class "Default")
      (node (ref "R69") (pin "2") (pinfunction "2_2") (pintype "passive"))
      (node (ref "VD10") (pin "1") (pinfunction "Anode_/_Cathode_1") (pintype "passive"))
    )
    (net (code "175") (name "Net-(VD11-Anode_{slash}_Cathode)") (class "Default")
      (node (ref "R70") (pin "2") (pinfunction "2_2") (pintype "passive"))
      (node (ref "VD11") (pin "1") (pinfunction "Anode_/_Cathode_1") (pintype "passive"))
    )
    (net (code "176") (name "Vref") (class "Default")
      (node (ref "C29") (pin "2") (pinfunction "2_2") (pintype "passive"))
      (node (ref "C48") (pin "2") (pinfunction "2_2") (pintype "passive"))
      (node (ref "U11") (pin "21") (pinfunction "VREF+_21") (pintype "passive"))
      (node (ref "U12") (pin "2") (pinfunction "OUT_2") (pintype "passive"))
      (node (ref "U6") (pin "7") (pinfunction "VREF1_7") (pintype "passive"))
    )
    (net (code "177") (name "unconnected-(J7-NC-Pad7)") (class "Default")
      (node (ref "J7") (pin "7") (pinfunction "NC_7") (pintype "passive"))
    )
    (net (code "178") (name "unconnected-(J7-PadSH1)") (class "Default")
      (node (ref "J7") (pin "SH1") (pinfunction "SH1_SH1") (pintype "passive"))
    )
    (net (code "179") (name "unconnected-(U7-NC-Pad4)") (class "Default")
      (node (ref "U7") (pin "4") (pinfunction "NC_4") (pintype "passive+no_connect"))
    )
    (net (code "180") (name "unconnected-(U7-NC-Pad5)") (class "Default")
      (node (ref "U7") (pin "5") (pinfunction "NC_5") (pintype "passive+no_connect"))
    )
    (net (code "181") (name "unconnected-(U7-NC-Pad11)") (class "Default")
      (node (ref "U7") (pin "11") (pinfunction "NC_11") (pintype "passive+no_connect"))
    )
    (net (code "182") (name "unconnected-(U7-NC-Pad14)") (class "Default")
      (node (ref "U7") (pin "14") (pinfunction "NC_14") (pintype "passive+no_connect"))
    )
  )
)
